# LR1302_LoRaWAN_Gateway_Module_V1_0_868SP.net
KiCad netlist of a schematic drawn in EAGLE
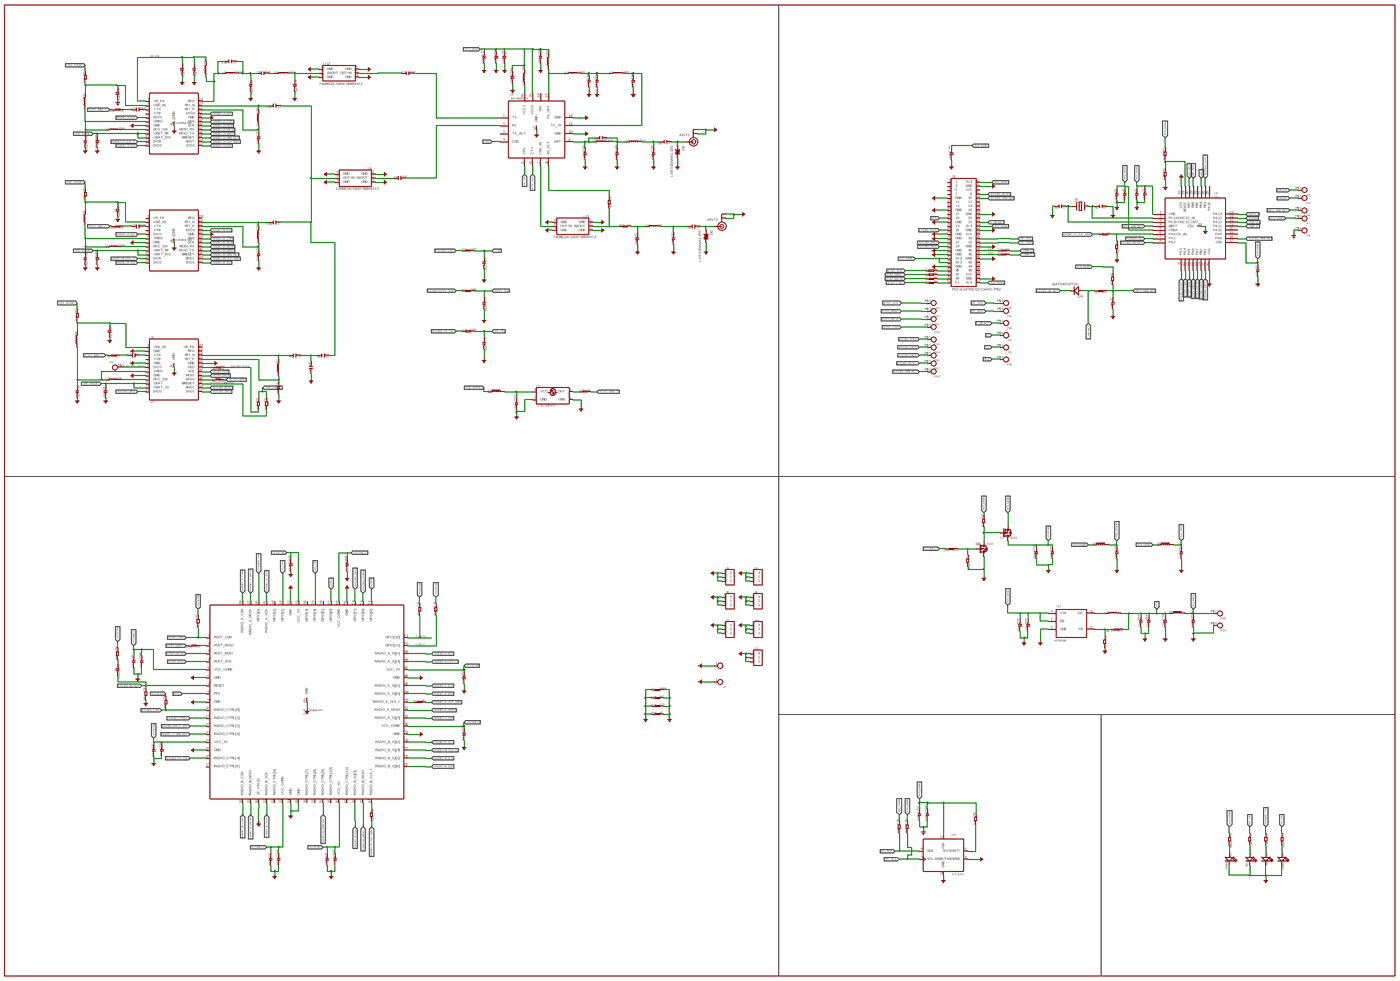
[diagram p0: schematic, sheet 1, overview]
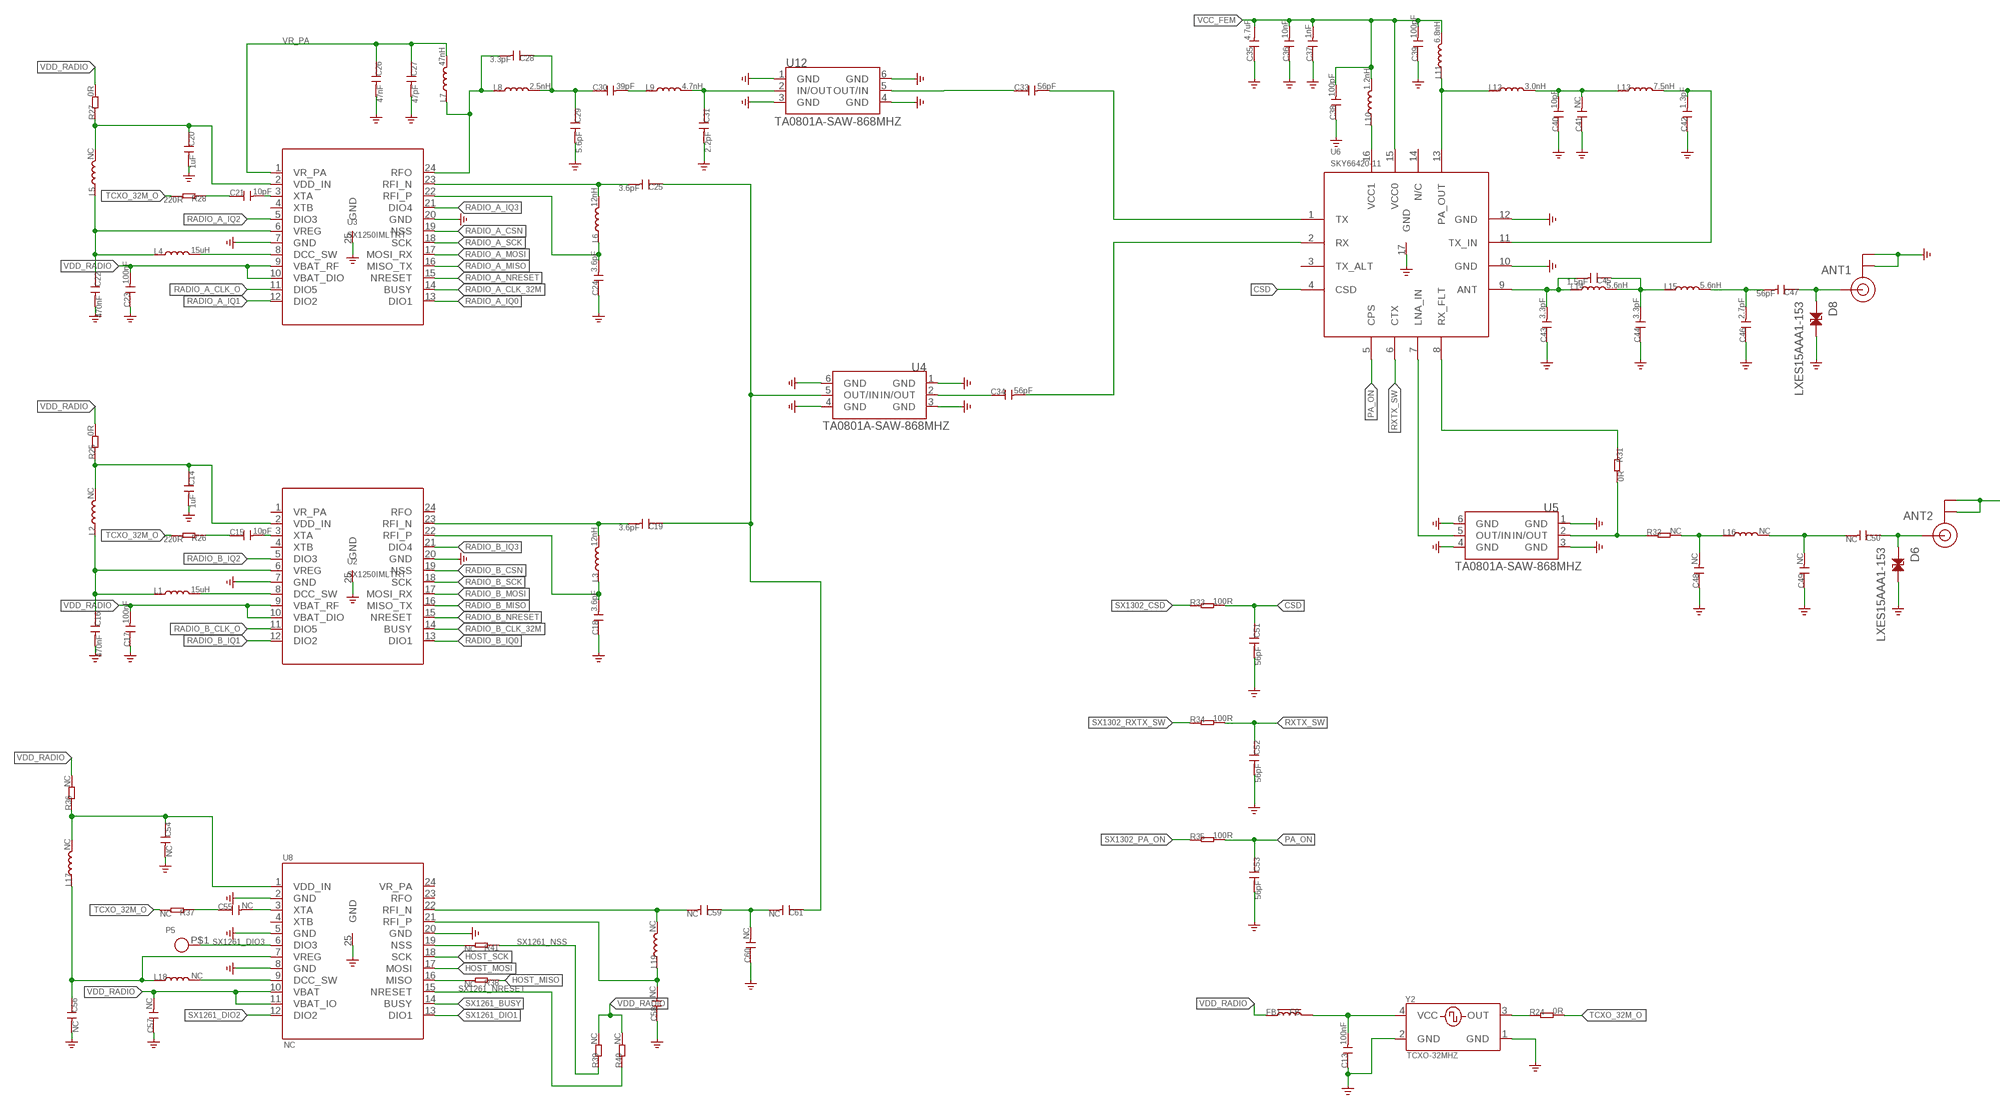
[diagram p1: schematic, sheet 1, part 1 of 4]
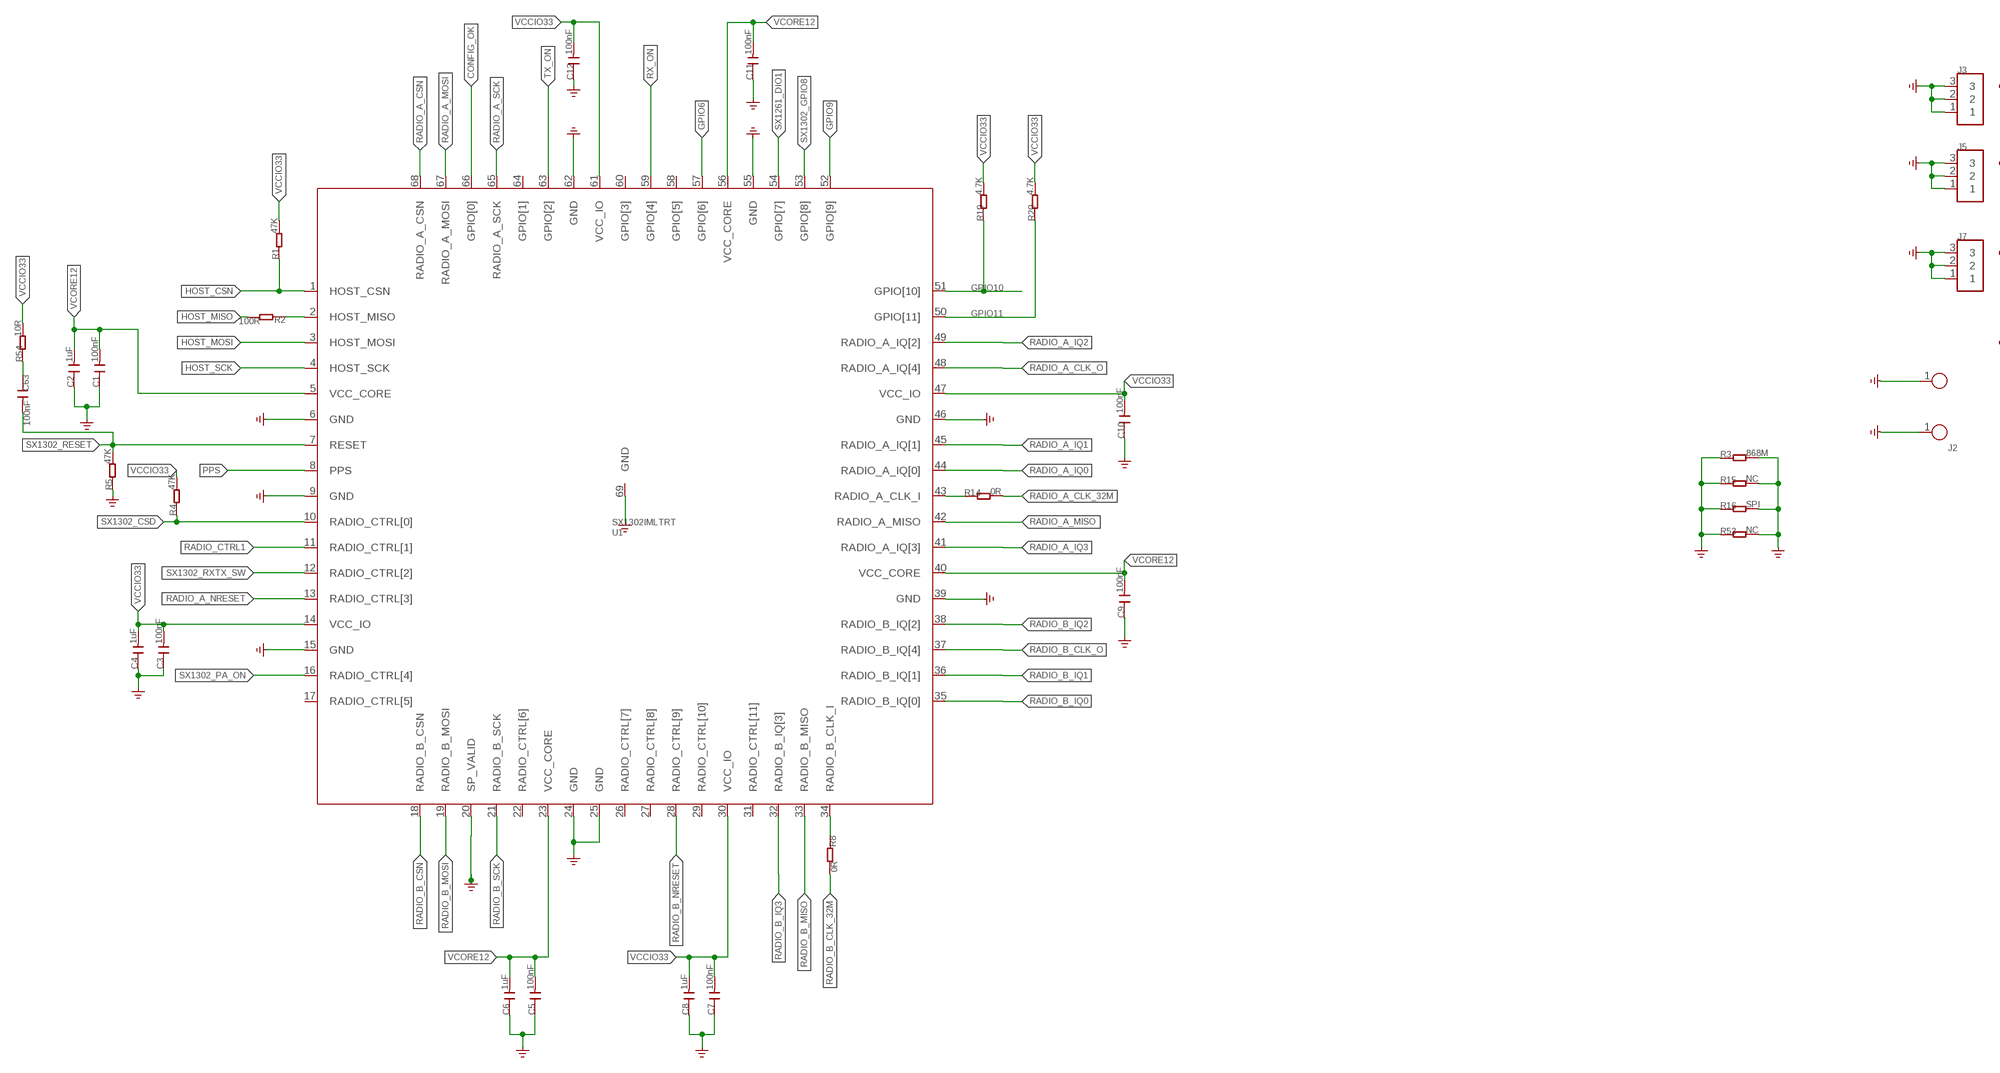
[diagram p2: schematic, sheet 1, part 2 of 4]
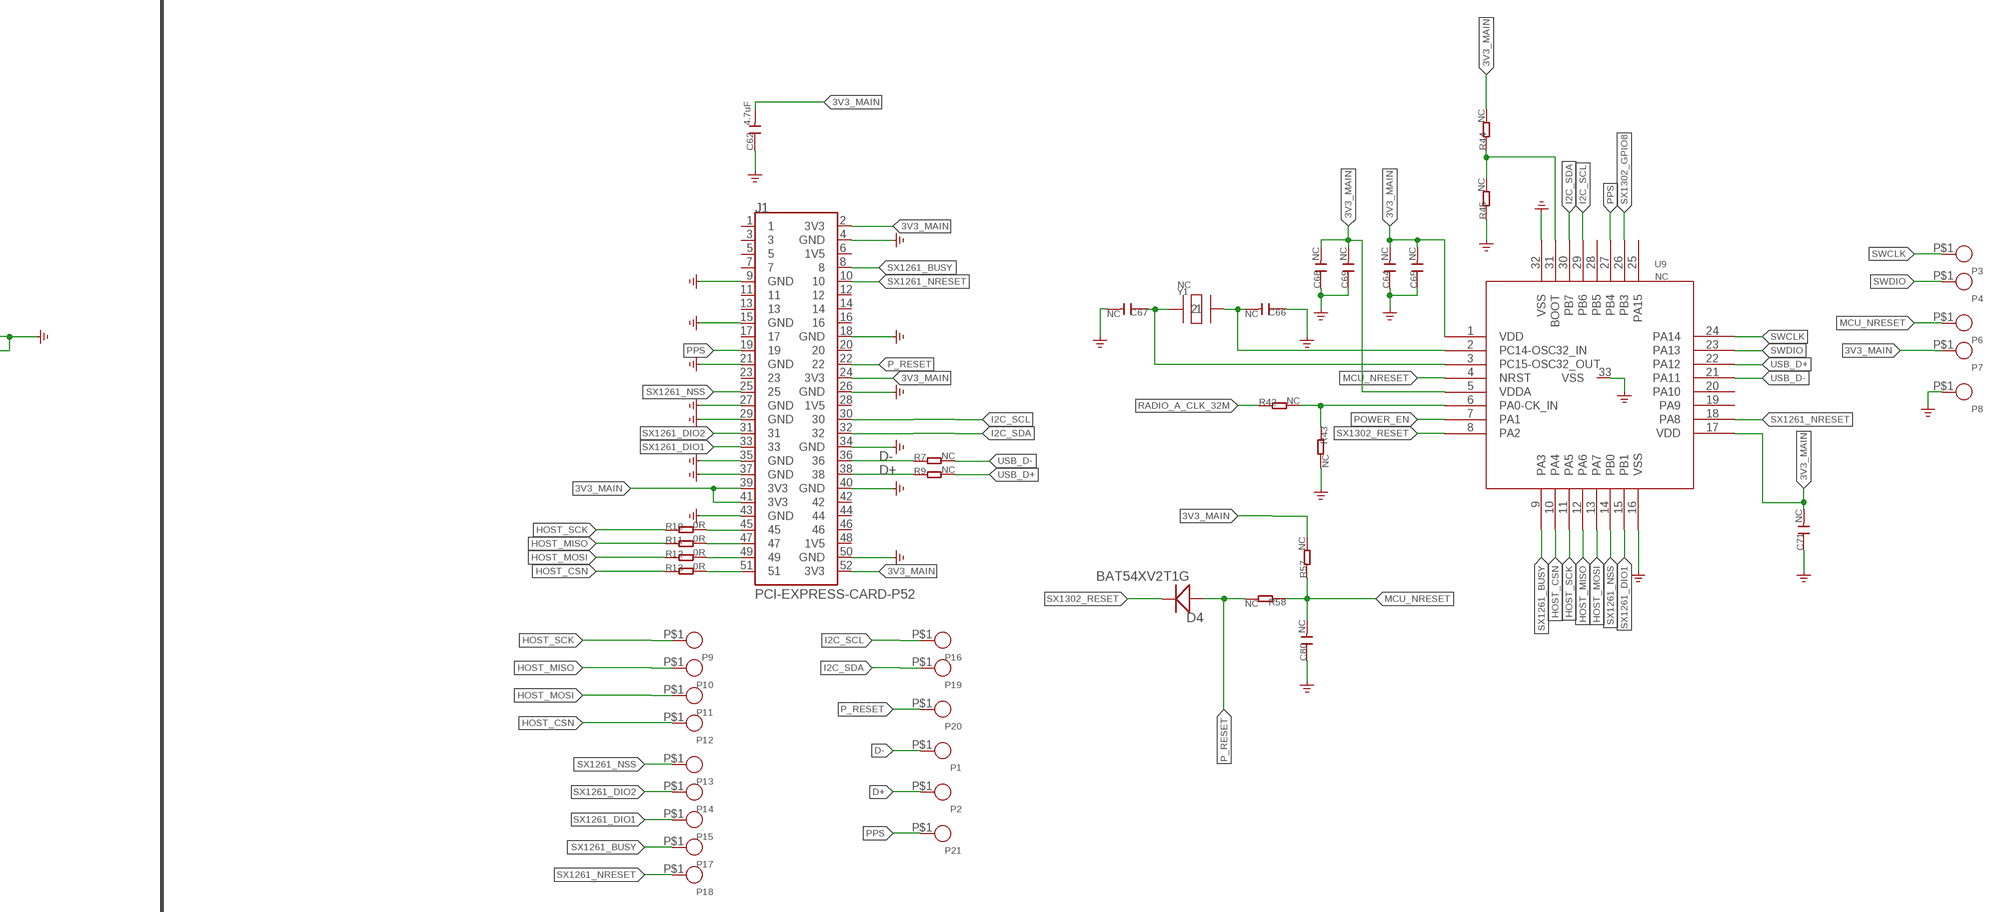
[diagram p3: schematic, sheet 1, part 3 of 4]
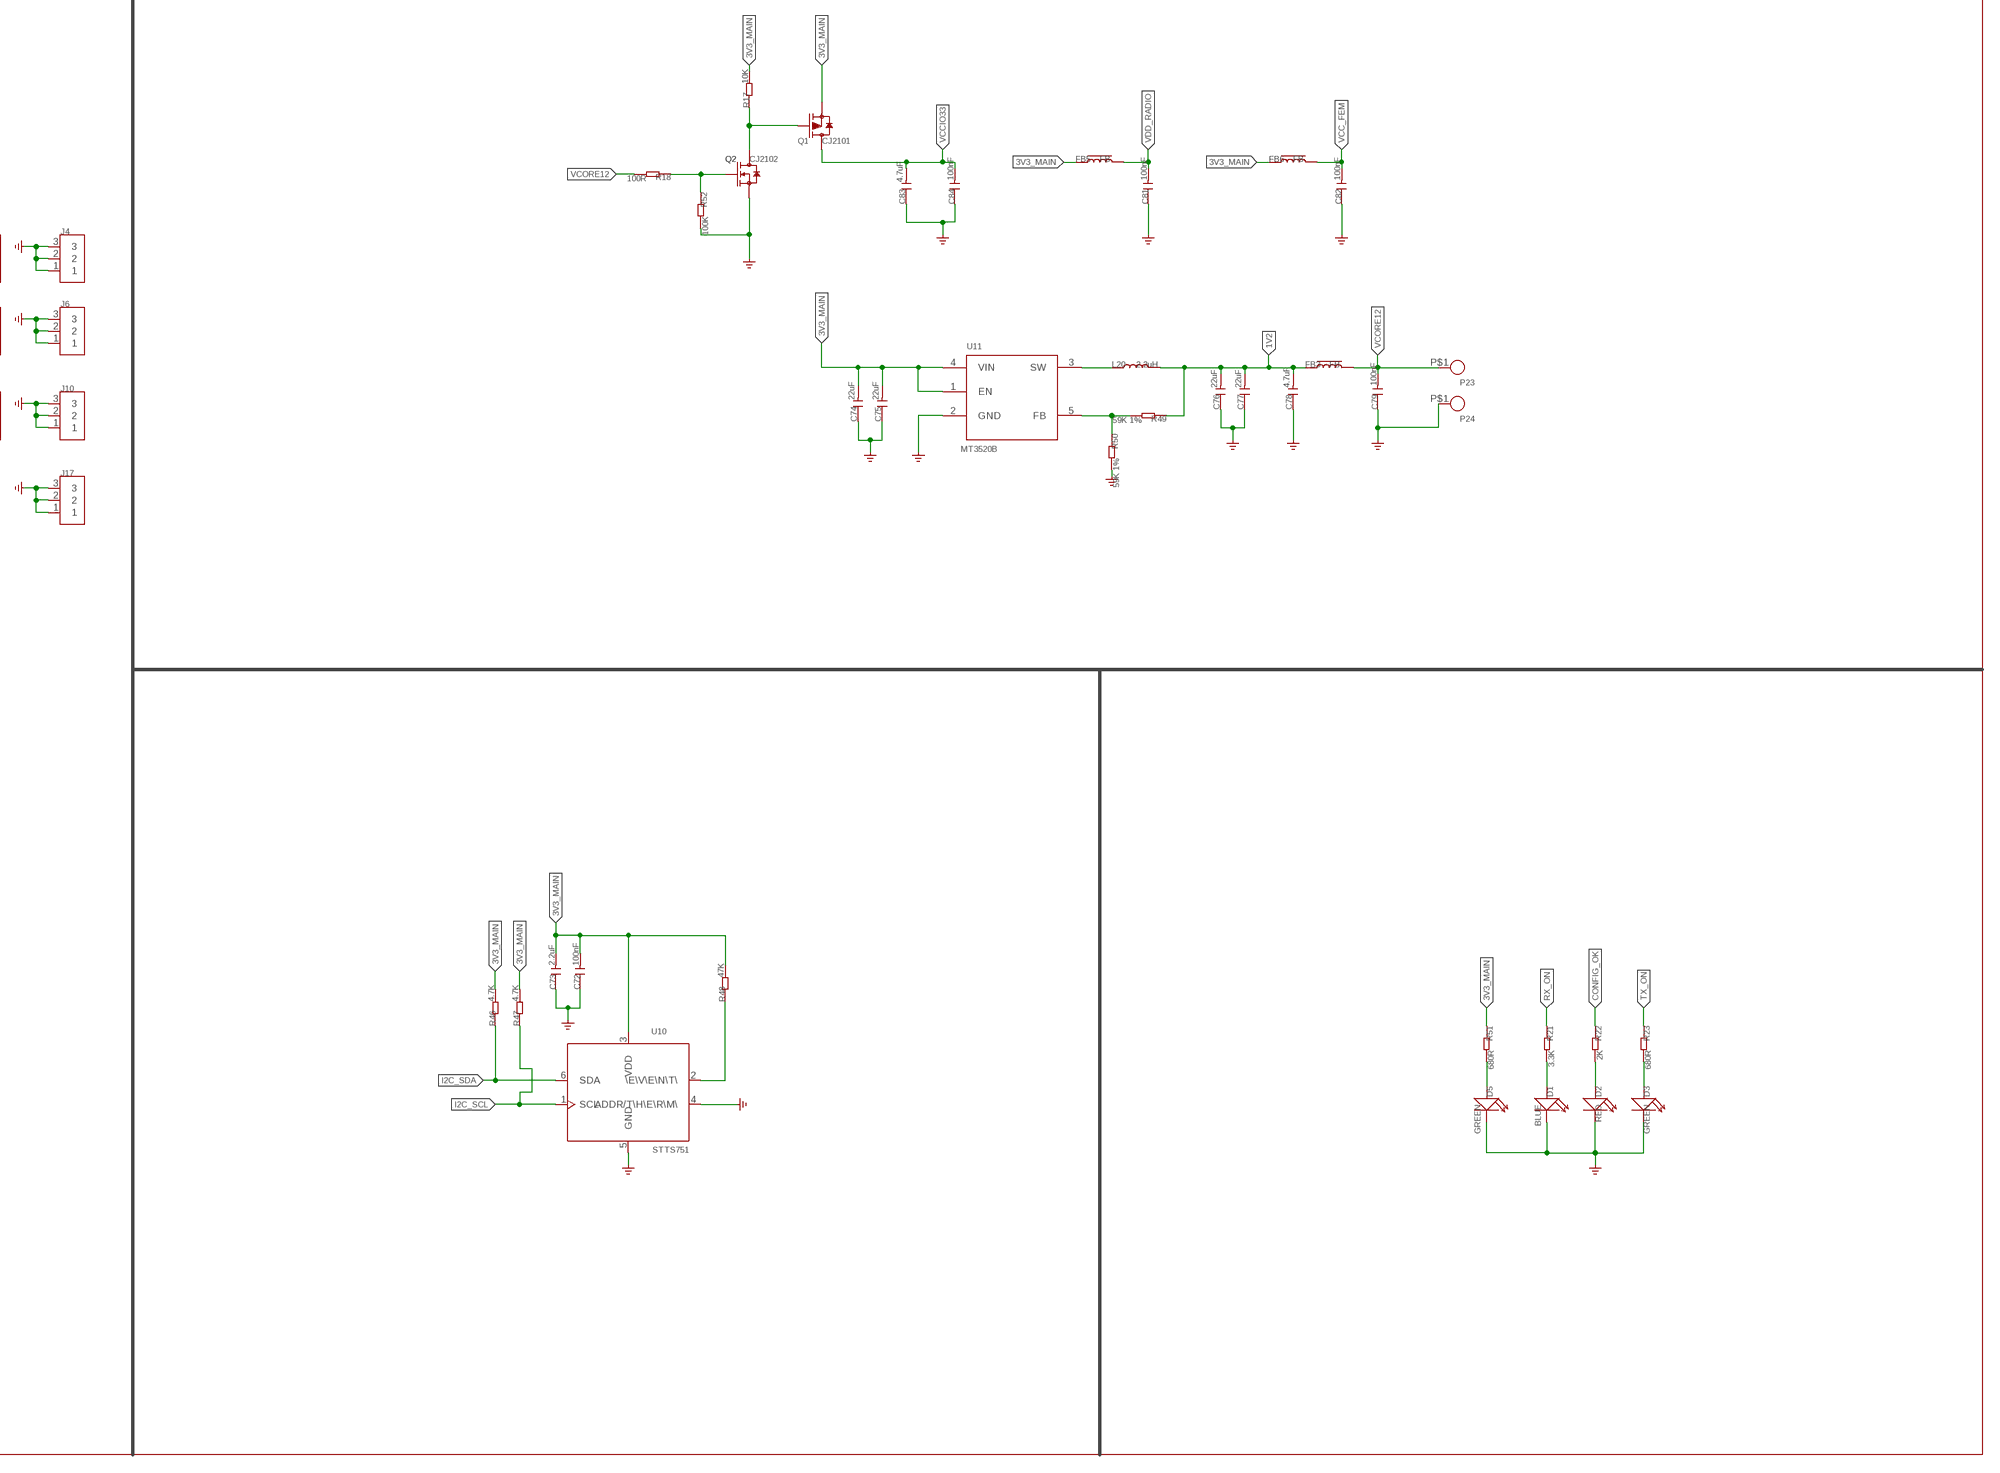
[diagram p4: schematic, sheet 1, part 4 of 4]

(export (version "E")
  (design (tool "Eeschema 10.0.6"))
  (components
    (comp (ref "ANT1")
      (value "U.FL_SMTU.FL-R-SMD")
      (footprint "eagle-import:U.FL-R-SMD")
      (libsource (lib "eagle-import") (part "U.FL_SMTU.FL-R-SMD"))
    )
    (comp (ref "ANT2")
      (value "NC")
      (footprint "eagle-import:U.FL-R-SMD")
      (libsource (lib "eagle-import") (part "U.FL_SMTU.FL-R-SMD"))
    )
    (comp (ref "C1")
      (value "100nF")
      (footprint "eagle-import:C0402")
      (libsource (lib "eagle-import") (part "CAPC0402-1"))
    )
    (comp (ref "C2")
      (value "1uF")
      (footprint "eagle-import:C0402")
      (libsource (lib "eagle-import") (part "CAPC0402-1"))
    )
    (comp (ref "C3")
      (value "100nF")
      (footprint "eagle-import:C0402")
      (libsource (lib "eagle-import") (part "CAPC0402-1"))
    )
    (comp (ref "C4")
      (value "1uF")
      (footprint "eagle-import:C0402")
      (libsource (lib "eagle-import") (part "CAPC0402-1"))
    )
    (comp (ref "C5")
      (value "100nF")
      (footprint "eagle-import:C0402")
      (libsource (lib "eagle-import") (part "CAPC0402-1"))
    )
    (comp (ref "C6")
      (value "1uF")
      (footprint "eagle-import:C0402")
      (libsource (lib "eagle-import") (part "CAPC0402-1"))
    )
    (comp (ref "C7")
      (value "100nF")
      (footprint "eagle-import:C0402")
      (libsource (lib "eagle-import") (part "CAPC0402-1"))
    )
    (comp (ref "C8")
      (value "1uF")
      (footprint "eagle-import:C0402")
      (libsource (lib "eagle-import") (part "CAPC0402-1"))
    )
    (comp (ref "C9")
      (value "100nF")
      (footprint "eagle-import:C0402")
      (libsource (lib "eagle-import") (part "CAPC0402-1"))
    )
    (comp (ref "C10")
      (value "100nF")
      (footprint "eagle-import:C0402")
      (libsource (lib "eagle-import") (part "CAPC0402-1"))
    )
    (comp (ref "C11")
      (value "100nF")
      (footprint "eagle-import:C0402")
      (libsource (lib "eagle-import") (part "CAPC0402-1"))
    )
    (comp (ref "C12")
      (value "100nF")
      (footprint "eagle-import:C0402")
      (libsource (lib "eagle-import") (part "CAPC0402-1"))
    )
    (comp (ref "C13")
      (value "100nF")
      (footprint "eagle-import:C0402")
      (libsource (lib "eagle-import") (part "CAPC0402-1"))
    )
    (comp (ref "C14")
      (value "1uF")
      (footprint "eagle-import:C0402")
      (libsource (lib "eagle-import") (part "CAPC0402-1"))
    )
    (comp (ref "C15")
      (value "10pF")
      (footprint "eagle-import:C0402")
      (libsource (lib "eagle-import") (part "CAPC0402-1"))
    )
    (comp (ref "C16")
      (value "470nF")
      (footprint "eagle-import:C0402")
      (libsource (lib "eagle-import") (part "CAPC0402-1"))
    )
    (comp (ref "C17")
      (value "100nF")
      (footprint "eagle-import:C0402")
      (libsource (lib "eagle-import") (part "CAPC0402-1"))
    )
    (comp (ref "C18")
      (value "3.6pF")
      (footprint "eagle-import:C0402")
      (libsource (lib "eagle-import") (part "CAPC0402-1"))
    )
    (comp (ref "C19")
      (value "3.6pF")
      (footprint "eagle-import:C0402")
      (libsource (lib "eagle-import") (part "CAPC0402-1"))
    )
    (comp (ref "C20")
      (value "1uF")
      (footprint "eagle-import:C0402")
      (libsource (lib "eagle-import") (part "CAPC0402-1"))
    )
    (comp (ref "C21")
      (value "10pF")
      (footprint "eagle-import:C0402")
      (libsource (lib "eagle-import") (part "CAPC0402-1"))
    )
    (comp (ref "C22")
      (value "470nF")
      (footprint "eagle-import:C0402")
      (libsource (lib "eagle-import") (part "CAPC0402-1"))
    )
    (comp (ref "C23")
      (value "100nF")
      (footprint "eagle-import:C0402")
      (libsource (lib "eagle-import") (part "CAPC0402-1"))
    )
    (comp (ref "C24")
      (value "3.6pF")
      (footprint "eagle-import:C0402")
      (libsource (lib "eagle-import") (part "CAPC0402-1"))
    )
    (comp (ref "C25")
      (value "3.6pF")
      (footprint "eagle-import:C0402")
      (libsource (lib "eagle-import") (part "CAPC0402-1"))
    )
    (comp (ref "C26")
      (value "47nF")
      (footprint "eagle-import:C0402")
      (libsource (lib "eagle-import") (part "CAPC0402-1"))
    )
    (comp (ref "C27")
      (value "47pF")
      (footprint "eagle-import:C0402")
      (libsource (lib "eagle-import") (part "CAPC0402-1"))
    )
    (comp (ref "C28")
      (value "3.3pF")
      (footprint "eagle-import:C0402")
      (libsource (lib "eagle-import") (part "CAPC0402-1"))
    )
    (comp (ref "C29")
      (value "5.6pF")
      (footprint "eagle-import:C0402")
      (libsource (lib "eagle-import") (part "CAPC0402-1"))
    )
    (comp (ref "C30")
      (value "39pF")
      (footprint "eagle-import:C0402")
      (libsource (lib "eagle-import") (part "CAPC0402-1"))
    )
    (comp (ref "C31")
      (value "2.2pF")
      (footprint "eagle-import:C0402")
      (libsource (lib "eagle-import") (part "CAPC0402-1"))
    )
    (comp (ref "C33")
      (value "56pF")
      (footprint "eagle-import:C0402")
      (libsource (lib "eagle-import") (part "CAPC0402-1"))
    )
    (comp (ref "C34")
      (value "56pF")
      (footprint "eagle-import:C0402")
      (libsource (lib "eagle-import") (part "CAPC0402-1"))
    )
    (comp (ref "C35")
      (value "4.7uF")
      (footprint "eagle-import:C0603")
      (libsource (lib "eagle-import") (part "CAP"))
    )
    (comp (ref "C36")
      (value "10nF")
      (footprint "eagle-import:C0402")
      (libsource (lib "eagle-import") (part "CAPC0402-1"))
    )
    (comp (ref "C37")
      (value "1nF")
      (footprint "eagle-import:C0402")
      (libsource (lib "eagle-import") (part "CAPC0402-1"))
    )
    (comp (ref "C38")
      (value "100pF")
      (footprint "eagle-import:C0402")
      (libsource (lib "eagle-import") (part "CAPC0402-1"))
    )
    (comp (ref "C39")
      (value "100pF")
      (footprint "eagle-import:C0402")
      (libsource (lib "eagle-import") (part "CAPC0402-1"))
    )
    (comp (ref "C40")
      (value "10pF")
      (footprint "eagle-import:C0402")
      (libsource (lib "eagle-import") (part "CAPC0402-1"))
    )
    (comp (ref "C41")
      (value "NC")
      (footprint "eagle-import:C0402")
      (libsource (lib "eagle-import") (part "CAPC0402-1"))
    )
    (comp (ref "C42")
      (value "1.3pF")
      (footprint "eagle-import:C0402")
      (libsource (lib "eagle-import") (part "CAPC0402-1"))
    )
    (comp (ref "C43")
      (value "3.3pF")
      (footprint "eagle-import:C0402")
      (libsource (lib "eagle-import") (part "CAPC0402-1"))
    )
    (comp (ref "C44")
      (value "3.3pF")
      (footprint "eagle-import:C0402")
      (libsource (lib "eagle-import") (part "CAPC0402-1"))
    )
    (comp (ref "C45")
      (value "1.5pF")
      (footprint "eagle-import:C0402")
      (libsource (lib "eagle-import") (part "CAPC0402-1"))
    )
    (comp (ref "C46")
      (value "2.7pF")
      (footprint "eagle-import:C0402")
      (libsource (lib "eagle-import") (part "CAPC0402-1"))
    )
    (comp (ref "C47")
      (value "56pF")
      (footprint "eagle-import:C0402")
      (libsource (lib "eagle-import") (part "CAPC0402-1"))
    )
    (comp (ref "C48")
      (value "NC")
      (footprint "eagle-import:C0402")
      (libsource (lib "eagle-import") (part "CAPC0402-1"))
    )
    (comp (ref "C49")
      (value "NC")
      (footprint "eagle-import:C0402")
      (libsource (lib "eagle-import") (part "CAPC0402-1"))
    )
    (comp (ref "C50")
      (value "NC")
      (footprint "eagle-import:C0402")
      (libsource (lib "eagle-import") (part "CAPC0402-1"))
    )
    (comp (ref "C51")
      (value "56pF")
      (footprint "eagle-import:C0402")
      (libsource (lib "eagle-import") (part "CAPC0402-1"))
    )
    (comp (ref "C52")
      (value "56pF")
      (footprint "eagle-import:C0402")
      (libsource (lib "eagle-import") (part "CAPC0402-1"))
    )
    (comp (ref "C53")
      (value "56pF")
      (footprint "eagle-import:C0402")
      (libsource (lib "eagle-import") (part "CAPC0402-1"))
    )
    (comp (ref "C54")
      (value "NC")
      (footprint "eagle-import:C0402")
      (libsource (lib "eagle-import") (part "CAPC0402-1"))
    )
    (comp (ref "C55")
      (value "NC")
      (footprint "eagle-import:C0402")
      (libsource (lib "eagle-import") (part "CAPC0402-1"))
    )
    (comp (ref "C56")
      (value "NC")
      (footprint "eagle-import:C0402")
      (libsource (lib "eagle-import") (part "CAPC0402-1"))
    )
    (comp (ref "C57")
      (value "NC")
      (footprint "eagle-import:C0402")
      (libsource (lib "eagle-import") (part "CAPC0402-1"))
    )
    (comp (ref "C58")
      (value "NC")
      (footprint "eagle-import:C0402")
      (libsource (lib "eagle-import") (part "CAPC0402-1"))
    )
    (comp (ref "C59")
      (value "NC")
      (footprint "eagle-import:C0402")
      (libsource (lib "eagle-import") (part "CAPC0402-1"))
    )
    (comp (ref "C60")
      (value "NC")
      (footprint "eagle-import:C0402")
      (libsource (lib "eagle-import") (part "CAPC0402-1"))
    )
    (comp (ref "C61")
      (value "NC")
      (footprint "eagle-import:C0402")
      (libsource (lib "eagle-import") (part "CAPC0402-1"))
    )
    (comp (ref "C62")
      (value "4.7uF")
      (footprint "eagle-import:C0603")
      (libsource (lib "eagle-import") (part "CAP"))
    )
    (comp (ref "C63")
      (value "100nF")
      (footprint "eagle-import:C0402")
      (libsource (lib "eagle-import") (part "CAPC0402-1"))
    )
    (comp (ref "C64")
      (value "NC")
      (footprint "eagle-import:C0402")
      (libsource (lib "eagle-import") (part "CAPC0402-1"))
    )
    (comp (ref "C65")
      (value "NC")
      (footprint "eagle-import:C0402")
      (libsource (lib "eagle-import") (part "CAPC0402-1"))
    )
    (comp (ref "C66")
      (value "NC")
      (footprint "eagle-import:C0402")
      (libsource (lib "eagle-import") (part "CAPC0402-1"))
    )
    (comp (ref "C67")
      (value "NC")
      (footprint "eagle-import:C0402")
      (libsource (lib "eagle-import") (part "CAPC0402-1"))
    )
    (comp (ref "C68")
      (value "NC")
      (footprint "eagle-import:C0402")
      (libsource (lib "eagle-import") (part "CAPC0402-1"))
    )
    (comp (ref "C69")
      (value "NC")
      (footprint "eagle-import:C0402")
      (libsource (lib "eagle-import") (part "CAPC0402-1"))
    )
    (comp (ref "C71")
      (value "NC")
      (footprint "eagle-import:C0402")
      (libsource (lib "eagle-import") (part "CAPC0402-1"))
    )
    (comp (ref "C72")
      (value "100nF")
      (footprint "eagle-import:C0402")
      (libsource (lib "eagle-import") (part "CAPC0402-1"))
    )
    (comp (ref "C73")
      (value "2.2uF")
      (footprint "eagle-import:C0402")
      (libsource (lib "eagle-import") (part "CAPC0402-1"))
    )
    (comp (ref "C74")
      (value "22uF")
      (footprint "eagle-import:C0603")
      (libsource (lib "eagle-import") (part "CAP"))
    )
    (comp (ref "C75")
      (value "22uF")
      (footprint "eagle-import:C0603")
      (libsource (lib "eagle-import") (part "CAP"))
    )
    (comp (ref "C76")
      (value "22uF")
      (footprint "eagle-import:C0603")
      (libsource (lib "eagle-import") (part "CAP"))
    )
    (comp (ref "C77")
      (value "22uF")
      (footprint "eagle-import:C0603")
      (libsource (lib "eagle-import") (part "CAP"))
    )
    (comp (ref "C78")
      (value "4.7uF")
      (footprint "eagle-import:C0603")
      (libsource (lib "eagle-import") (part "CAP"))
    )
    (comp (ref "C79")
      (value "100nF")
      (footprint "eagle-import:C0402")
      (libsource (lib "eagle-import") (part "CAPC0402-1"))
    )
    (comp (ref "C80")
      (value "NC")
      (footprint "eagle-import:C0402")
      (libsource (lib "eagle-import") (part "CAPC0402-1"))
    )
    (comp (ref "C81")
      (value "100nF")
      (footprint "eagle-import:C0402")
      (libsource (lib "eagle-import") (part "CAPC0402-1"))
    )
    (comp (ref "C82")
      (value "100nF")
      (footprint "eagle-import:C0402")
      (libsource (lib "eagle-import") (part "CAPC0402-1"))
    )
    (comp (ref "C83")
      (value "4.7uF")
      (footprint "eagle-import:C0603")
      (libsource (lib "eagle-import") (part "CAP"))
    )
    (comp (ref "C84")
      (value "100nF")
      (footprint "eagle-import:C0402")
      (libsource (lib "eagle-import") (part "CAPC0402-1"))
    )
    (comp (ref "D1")
      (value "BLUE")
      (footprint "eagle-import:LED-0402")
      (libsource (lib "eagle-import") (part "LED-SMT"))
    )
    (comp (ref "D2")
      (value "RED")
      (footprint "eagle-import:LED-0402")
      (libsource (lib "eagle-import") (part "LED-SMT"))
    )
    (comp (ref "D3")
      (value "GREEN")
      (footprint "eagle-import:LED-0402")
      (libsource (lib "eagle-import") (part "LED-SMT"))
    )
    (comp (ref "D4")
      (value "BAT54XV2T1G")
      (footprint "eagle-import:D_SOD523")
      (libsource (lib "eagle-import") (part "DIODE0603"))
    )
    (comp (ref "D5")
      (value "GREEN")
      (footprint "eagle-import:LED-0402")
      (libsource (lib "eagle-import") (part "LED-SMT"))
    )
    (comp (ref "D6")
      (value "LXES15AAA1-153")
      (footprint "eagle-import:D0402")
      (libsource (lib "eagle-import") (part "PESD0402"))
    )
    (comp (ref "D8")
      (value "LXES15AAA1-153")
      (footprint "eagle-import:D0402")
      (libsource (lib "eagle-import") (part "PESD0402"))
    )
    (comp (ref "FB1")
      (value "FB")
      (footprint "eagle-import:L0402")
      (libsource (lib "eagle-import") (part "FB"))
    )
    (comp (ref "FB3")
      (value "FB")
      (footprint "eagle-import:L0402")
      (libsource (lib "eagle-import") (part "FB"))
    )
    (comp (ref "FB5")
      (value "FB")
      (footprint "eagle-import:L0402")
      (libsource (lib "eagle-import") (part "FB"))
    )
    (comp (ref "FB6")
      (value "FB")
      (footprint "eagle-import:L0402")
      (libsource (lib "eagle-import") (part "FB"))
    )
    (comp (ref "J1")
      (value "PCI-EXPRESS-CARD-P52")
      (footprint "eagle-import:PCIE-MINI-S52")
      (libsource (lib "eagle-import") (part "PCI-EXPRESS-CARD-P52"))
    )
    (comp (ref "J2")
      (value "PAD-THO-2.65MM")
      (footprint "eagle-import:PAD-THO-2.6_5MM")
      (libsource (lib "eagle-import") (part "PAD-THO-2.65MM"))
    )
    (comp (ref "J3")
      (value "PBJ-ICSRC6508-SMD")
      (footprint "eagle-import:PBJ-ICSRC6508-SMD")
      (libsource (lib "eagle-import") (part "PBJ-ICSRC6508-SMD"))
    )
    (comp (ref "J4")
      (value "PBJ-ICSRC6508-SMD")
      (footprint "eagle-import:PBJ-ICSRC6508-SMD")
      (libsource (lib "eagle-import") (part "PBJ-ICSRC6508-SMD"))
    )
    (comp (ref "J5")
      (value "PBJ-ICSRC6508-SMD")
      (footprint "eagle-import:PBJ-ICSRC6508-SMD")
      (libsource (lib "eagle-import") (part "PBJ-ICSRC6508-SMD"))
    )
    (comp (ref "J6")
      (value "PBJ-ICSRC6508-SMD")
      (footprint "eagle-import:PBJ-ICSRC6508-SMD")
      (libsource (lib "eagle-import") (part "PBJ-ICSRC6508-SMD"))
    )
    (comp (ref "J7")
      (value "PBJ-ICSRC6508-SMD")
      (footprint "eagle-import:PBJ-ICSRC6508-SMD")
      (libsource (lib "eagle-import") (part "PBJ-ICSRC6508-SMD"))
    )
    (comp (ref "J10")
      (value "PBJ-ICSRC6508-SMD")
      (footprint "eagle-import:PBJ-ICSRC6508-SMD")
      (libsource (lib "eagle-import") (part "PBJ-ICSRC6508-SMD"))
    )
    (comp (ref "J11")
      (value "PAD-THO-2.65MM")
      (footprint "eagle-import:PAD-THO-2.6_5MM")
      (libsource (lib "eagle-import") (part "PAD-THO-2.65MM"))
    )
    (comp (ref "J17")
      (value "PBJ-ICSRC6508-SMD")
      (footprint "eagle-import:PBJ-ICSRC6508-SMD")
      (libsource (lib "eagle-import") (part "PBJ-ICSRC6508-SMD"))
    )
    (comp (ref "L1")
      (value "15uH")
      (footprint "eagle-import:L0805")
      (libsource (lib "eagle-import") (part "L0805"))
    )
    (comp (ref "L2")
      (value "NC")
      (footprint "eagle-import:L0402")
      (libsource (lib "eagle-import") (part "L0402"))
    )
    (comp (ref "L3")
      (value "12nH")
      (footprint "eagle-import:L0402")
      (libsource (lib "eagle-import") (part "L0402"))
    )
    (comp (ref "L4")
      (value "15uH")
      (footprint "eagle-import:L0805")
      (libsource (lib "eagle-import") (part "L0805"))
    )
    (comp (ref "L5")
      (value "NC")
      (footprint "eagle-import:L0402")
      (libsource (lib "eagle-import") (part "L0402"))
    )
    (comp (ref "L6")
      (value "12nH")
      (footprint "eagle-import:L0402")
      (libsource (lib "eagle-import") (part "L0402"))
    )
    (comp (ref "L7")
      (value "47nH")
      (footprint "eagle-import:L0402")
      (libsource (lib "eagle-import") (part "L0402"))
    )
    (comp (ref "L8")
      (value "2.5nH")
      (footprint "eagle-import:L0402")
      (libsource (lib "eagle-import") (part "L0402"))
    )
    (comp (ref "L9")
      (value "4.7nH")
      (footprint "eagle-import:L0402")
      (libsource (lib "eagle-import") (part "L0402"))
    )
    (comp (ref "L10")
      (value "1.2nH")
      (footprint "eagle-import:L0402")
      (libsource (lib "eagle-import") (part "L0402"))
    )
    (comp (ref "L11")
      (value "6.8nH")
      (footprint "eagle-import:L0402")
      (libsource (lib "eagle-import") (part "L0402"))
    )
    (comp (ref "L12")
      (value "3.0nH")
      (footprint "eagle-import:L0402")
      (libsource (lib "eagle-import") (part "L0402"))
    )
    (comp (ref "L13")
      (value "7.5nH")
      (footprint "eagle-import:L0402")
      (libsource (lib "eagle-import") (part "L0402"))
    )
    (comp (ref "L14")
      (value "5.6nH")
      (footprint "eagle-import:L0402")
      (libsource (lib "eagle-import") (part "L0402"))
    )
    (comp (ref "L15")
      (value "5.6nH")
      (footprint "eagle-import:L0402")
      (libsource (lib "eagle-import") (part "L0402"))
    )
    (comp (ref "L16")
      (value "NC")
      (footprint "eagle-import:L0402")
      (libsource (lib "eagle-import") (part "L0402"))
    )
    (comp (ref "L17")
      (value "NC")
      (footprint "eagle-import:L0402")
      (libsource (lib "eagle-import") (part "L0402"))
    )
    (comp (ref "L18")
      (value "NC")
      (footprint "eagle-import:L0805")
      (libsource (lib "eagle-import") (part "L0805"))
    )
    (comp (ref "L19")
      (value "NC")
      (footprint "eagle-import:L0402")
      (libsource (lib "eagle-import") (part "L0402"))
    )
    (comp (ref "L20")
      (value "2.2uH")
      (footprint "eagle-import:L3015_SMD")
      (libsource (lib "eagle-import") (part "L"))
    )
    (comp (ref "P1")
      (value "TEST_PADPAD-1.0MM")
      (footprint "eagle-import:TEST_PAD-1.0MM")
      (libsource (lib "eagle-import") (part "TEST_PADPAD-1.0MM"))
    )
    (comp (ref "P2")
      (value "TEST_PADPAD-1.0MM")
      (footprint "eagle-import:TEST_PAD-1.0MM")
      (libsource (lib "eagle-import") (part "TEST_PADPAD-1.0MM"))
    )
    (comp (ref "P3")
      (value "TEST_PADPAD-1.0MM")
      (footprint "eagle-import:TEST_PAD-1.0MM")
      (libsource (lib "eagle-import") (part "TEST_PADPAD-1.0MM"))
    )
    (comp (ref "P4")
      (value "TEST_PADPAD-1.0MM")
      (footprint "eagle-import:TEST_PAD-1.0MM")
      (libsource (lib "eagle-import") (part "TEST_PADPAD-1.0MM"))
    )
    (comp (ref "P5")
      (value "TEST_PADPAD-1.0MM")
      (footprint "eagle-import:TEST_PAD-1.0MM")
      (libsource (lib "eagle-import") (part "TEST_PADPAD-1.0MM"))
    )
    (comp (ref "P6")
      (value "TEST_PADPAD-1.0MM")
      (footprint "eagle-import:TEST_PAD-1.0MM")
      (libsource (lib "eagle-import") (part "TEST_PADPAD-1.0MM"))
    )
    (comp (ref "P7")
      (value "TEST_PADPAD-1.0MM")
      (footprint "eagle-import:TEST_PAD-1.0MM")
      (libsource (lib "eagle-import") (part "TEST_PADPAD-1.0MM"))
    )
    (comp (ref "P8")
      (value "TEST_PADPAD-1.0MM")
      (footprint "eagle-import:TEST_PAD-1.0MM")
      (libsource (lib "eagle-import") (part "TEST_PADPAD-1.0MM"))
    )
    (comp (ref "P9")
      (value "TEST_PADPAD-1.0MM")
      (footprint "eagle-import:TEST_PAD-1.0MM")
      (libsource (lib "eagle-import") (part "TEST_PADPAD-1.0MM"))
    )
    (comp (ref "P10")
      (value "TEST_PADPAD-1.0MM")
      (footprint "eagle-import:TEST_PAD-1.0MM")
      (libsource (lib "eagle-import") (part "TEST_PADPAD-1.0MM"))
    )
    (comp (ref "P11")
      (value "TEST_PADPAD-1.0MM")
      (footprint "eagle-import:TEST_PAD-1.0MM")
      (libsource (lib "eagle-import") (part "TEST_PADPAD-1.0MM"))
    )
    (comp (ref "P12")
      (value "TEST_PADPAD-1.0MM")
      (footprint "eagle-import:TEST_PAD-1.0MM")
      (libsource (lib "eagle-import") (part "TEST_PADPAD-1.0MM"))
    )
    (comp (ref "P13")
      (value "TEST_PADPAD-1.0MM")
      (footprint "eagle-import:TEST_PAD-1.0MM")
      (libsource (lib "eagle-import") (part "TEST_PADPAD-1.0MM"))
    )
    (comp (ref "P14")
      (value "TEST_PADPAD-1.0MM")
      (footprint "eagle-import:TEST_PAD-1.0MM")
      (libsource (lib "eagle-import") (part "TEST_PADPAD-1.0MM"))
    )
    (comp (ref "P15")
      (value "TEST_PADPAD-1.0MM")
      (footprint "eagle-import:TEST_PAD-1.0MM")
      (libsource (lib "eagle-import") (part "TEST_PADPAD-1.0MM"))
    )
    (comp (ref "P16")
      (value "TEST_PADPAD-1.0MM")
      (footprint "eagle-import:TEST_PAD-1.0MM")
      (libsource (lib "eagle-import") (part "TEST_PADPAD-1.0MM"))
    )
    (comp (ref "P17")
      (value "TEST_PADPAD-1.0MM")
      (footprint "eagle-import:TEST_PAD-1.0MM")
      (libsource (lib "eagle-import") (part "TEST_PADPAD-1.0MM"))
    )
    (comp (ref "P18")
      (value "TEST_PADPAD-1.0MM")
      (footprint "eagle-import:TEST_PAD-1.0MM")
      (libsource (lib "eagle-import") (part "TEST_PADPAD-1.0MM"))
    )
    (comp (ref "P19")
      (value "TEST_PADPAD-1.0MM")
      (footprint "eagle-import:TEST_PAD-1.0MM")
      (libsource (lib "eagle-import") (part "TEST_PADPAD-1.0MM"))
    )
    (comp (ref "P20")
      (value "TEST_PADPAD-1.0MM")
      (footprint "eagle-import:TEST_PAD-1.0MM")
      (libsource (lib "eagle-import") (part "TEST_PADPAD-1.0MM"))
    )
    (comp (ref "P21")
      (value "TEST_PADPAD-1.0MM")
      (footprint "eagle-import:TEST_PAD-1.0MM")
      (libsource (lib "eagle-import") (part "TEST_PADPAD-1.0MM"))
    )
    (comp (ref "P23")
      (value "TEST_PADPAD-1.0MM")
      (footprint "eagle-import:TEST_PAD-1.0MM")
      (libsource (lib "eagle-import") (part "TEST_PADPAD-1.0MM"))
    )
    (comp (ref "P24")
      (value "TEST_PADPAD-1.0MM")
      (footprint "eagle-import:TEST_PAD-1.0MM")
      (libsource (lib "eagle-import") (part "TEST_PADPAD-1.0MM"))
    )
    (comp (ref "Q1")
      (value "CJ2101")
      (footprint "eagle-import:MOS_SOT323")
      (libsource (lib "eagle-import") (part "MOSFET-P"))
    )
    (comp (ref "Q2")
      (value "CJ2102")
      (footprint "eagle-import:MOS_SOT323")
      (libsource (lib "eagle-import") (part "MOSFET-NSI1304BDL"))
    )
    (comp (ref "R1")
      (value "47K")
      (footprint "eagle-import:R0402")
      (libsource (lib "eagle-import") (part "RES-0402"))
    )
    (comp (ref "R2")
      (value "100R")
      (footprint "eagle-import:R0402")
      (libsource (lib "eagle-import") (part "RES-0402"))
    )
    (comp (ref "R3")
      (value "868M")
      (footprint "eagle-import:R0402")
      (libsource (lib "eagle-import") (part "RES-0402"))
    )
    (comp (ref "R4")
      (value "47K")
      (footprint "eagle-import:R0402")
      (libsource (lib "eagle-import") (part "RES-0402"))
    )
    (comp (ref "R5")
      (value "47K")
      (footprint "eagle-import:R0402")
      (libsource (lib "eagle-import") (part "RES-0402"))
    )
    (comp (ref "R7")
      (value "NC")
      (footprint "eagle-import:R0402")
      (libsource (lib "eagle-import") (part "RES-0402"))
    )
    (comp (ref "R8")
      (value "0R")
      (footprint "eagle-import:R0402")
      (libsource (lib "eagle-import") (part "RES-0402"))
    )
    (comp (ref "R9")
      (value "NC")
      (footprint "eagle-import:R0402")
      (libsource (lib "eagle-import") (part "RES-0402"))
    )
    (comp (ref "R10")
      (value "0R")
      (footprint "eagle-import:R0402")
      (libsource (lib "eagle-import") (part "RES-0402"))
    )
    (comp (ref "R11")
      (value "0R")
      (footprint "eagle-import:R0402")
      (libsource (lib "eagle-import") (part "RES-0402"))
    )
    (comp (ref "R12")
      (value "0R")
      (footprint "eagle-import:R0402")
      (libsource (lib "eagle-import") (part "RES-0402"))
    )
    (comp (ref "R13")
      (value "0R")
      (footprint "eagle-import:R0402")
      (libsource (lib "eagle-import") (part "RES-0402"))
    )
    (comp (ref "R14")
      (value "0R")
      (footprint "eagle-import:R0402")
      (libsource (lib "eagle-import") (part "RES-0402"))
    )
    (comp (ref "R15")
      (value "NC")
      (footprint "eagle-import:R0402")
      (libsource (lib "eagle-import") (part "RES-0402"))
    )
    (comp (ref "R16")
      (value "SPI")
      (footprint "eagle-import:R0402")
      (libsource (lib "eagle-import") (part "RES-0402"))
    )
    (comp (ref "R17")
      (value "10K")
      (footprint "eagle-import:R0402")
      (libsource (lib "eagle-import") (part "RES-0402"))
    )
    (comp (ref "R18")
      (value "100R")
      (footprint "eagle-import:R0402")
      (libsource (lib "eagle-import") (part "RES-0402"))
    )
    (comp (ref "R19")
      (value "4.7K")
      (footprint "eagle-import:R0402")
      (libsource (lib "eagle-import") (part "RES-0402"))
    )
    (comp (ref "R20")
      (value "4.7K")
      (footprint "eagle-import:R0402")
      (libsource (lib "eagle-import") (part "RES-0402"))
    )
    (comp (ref "R21")
      (value "3.3K")
      (footprint "eagle-import:R0402")
      (libsource (lib "eagle-import") (part "RES-0402"))
    )
    (comp (ref "R22")
      (value "2K")
      (footprint "eagle-import:R0402")
      (libsource (lib "eagle-import") (part "RES-0402"))
    )
    (comp (ref "R23")
      (value "680R")
      (footprint "eagle-import:R0402")
      (libsource (lib "eagle-import") (part "RES-0402"))
    )
    (comp (ref "R24")
      (value "0R")
      (footprint "eagle-import:R0402")
      (libsource (lib "eagle-import") (part "RES-0402"))
    )
    (comp (ref "R25")
      (value "0R")
      (footprint "eagle-import:R0402")
      (libsource (lib "eagle-import") (part "RES-0402"))
    )
    (comp (ref "R26")
      (value "220R")
      (footprint "eagle-import:R0402")
      (libsource (lib "eagle-import") (part "RES-0402"))
    )
    (comp (ref "R27")
      (value "0R")
      (footprint "eagle-import:R0402")
      (libsource (lib "eagle-import") (part "RES-0402"))
    )
    (comp (ref "R28")
      (value "220R")
      (footprint "eagle-import:R0402")
      (libsource (lib "eagle-import") (part "RES-0402"))
    )
    (comp (ref "R31")
      (value "0R")
      (footprint "eagle-import:R0402")
      (libsource (lib "eagle-import") (part "RES-0402"))
    )
    (comp (ref "R32")
      (value "NC")
      (footprint "eagle-import:R0402")
      (libsource (lib "eagle-import") (part "RES-0402"))
    )
    (comp (ref "R33")
      (value "100R")
      (footprint "eagle-import:R0402")
      (libsource (lib "eagle-import") (part "RES-0402"))
    )
    (comp (ref "R34")
      (value "100R")
      (footprint "eagle-import:R0402")
      (libsource (lib "eagle-import") (part "RES-0402"))
    )
    (comp (ref "R35")
      (value "100R")
      (footprint "eagle-import:R0402")
      (libsource (lib "eagle-import") (part "RES-0402"))
    )
    (comp (ref "R36")
      (value "NC")
      (footprint "eagle-import:R0402")
      (libsource (lib "eagle-import") (part "RES-0402"))
    )
    (comp (ref "R37")
      (value "NC")
      (footprint "eagle-import:R0402")
      (libsource (lib "eagle-import") (part "RES-0402"))
    )
    (comp (ref "R38")
      (value "NC")
      (footprint "eagle-import:R0402")
      (libsource (lib "eagle-import") (part "RES-0402"))
    )
    (comp (ref "R39")
      (value "NC")
      (footprint "eagle-import:R0402")
      (libsource (lib "eagle-import") (part "RES-0402"))
    )
    (comp (ref "R40")
      (value "NC")
      (footprint "eagle-import:R0402")
      (libsource (lib "eagle-import") (part "RES-0402"))
    )
    (comp (ref "R41")
      (value "NC")
      (footprint "eagle-import:R0402")
      (libsource (lib "eagle-import") (part "RES-0402"))
    )
    (comp (ref "R42")
      (value "NC")
      (footprint "eagle-import:R0402")
      (libsource (lib "eagle-import") (part "RES-0402"))
    )
    (comp (ref "R43")
      (value "NC")
      (footprint "eagle-import:R0402")
      (libsource (lib "eagle-import") (part "RES-0402"))
    )
    (comp (ref "R44")
      (value "NC")
      (footprint "eagle-import:R0402")
      (libsource (lib "eagle-import") (part "RES-0402"))
    )
    (comp (ref "R45")
      (value "NC")
      (footprint "eagle-import:R0402")
      (libsource (lib "eagle-import") (part "RES-0402"))
    )
    (comp (ref "R46")
      (value "4.7K")
      (footprint "eagle-import:R0402")
      (libsource (lib "eagle-import") (part "RES-0402"))
    )
    (comp (ref "R47")
      (value "4.7K")
      (footprint "eagle-import:R0402")
      (libsource (lib "eagle-import") (part "RES-0402"))
    )
    (comp (ref "R48")
      (value "47K")
      (footprint "eagle-import:R0402")
      (libsource (lib "eagle-import") (part "RES-0402"))
    )
    (comp (ref "R49")
      (value "59K 1%")
      (footprint "eagle-import:R0402")
      (libsource (lib "eagle-import") (part "RES-0402"))
    )
    (comp (ref "R50")
      (value "59K 1%")
      (footprint "eagle-import:R0402")
      (libsource (lib "eagle-import") (part "RES-0402"))
    )
    (comp (ref "R51")
      (value "680R")
      (footprint "eagle-import:R0402")
      (libsource (lib "eagle-import") (part "RES-0402"))
    )
    (comp (ref "R52")
      (value "100K")
      (footprint "eagle-import:R0402")
      (libsource (lib "eagle-import") (part "RES-0402"))
    )
    (comp (ref "R53")
      (value "NC")
      (footprint "eagle-import:R0402")
      (libsource (lib "eagle-import") (part "RES-0402"))
    )
    (comp (ref "R54")
      (value "10R")
      (footprint "eagle-import:R0402")
      (libsource (lib "eagle-import") (part "RES-0402"))
    )
    (comp (ref "R57")
      (value "NC")
      (footprint "eagle-import:R0402")
      (libsource (lib "eagle-import") (part "RES-0402"))
    )
    (comp (ref "R58")
      (value "NC")
      (footprint "eagle-import:R0402")
      (libsource (lib "eagle-import") (part "RES-0402"))
    )
    (comp (ref "U1")
      (value "SX1302IMLTRT")
      (footprint "eagle-import:QFN68-7_7MM")
      (libsource (lib "eagle-import") (part "SX1302IMLTRT"))
    )
    (comp (ref "U2")
      (value "SX1250IMLTRT")
      (footprint "eagle-import:QFN24-4_4MM")
      (libsource (lib "eagle-import") (part "SX1250IMLTRT"))
    )
    (comp (ref "U3")
      (value "SX1250IMLTRT")
      (footprint "eagle-import:QFN24-4_4MM")
      (libsource (lib "eagle-import") (part "SX1250IMLTRT"))
    )
    (comp (ref "U4")
      (value "TA0801A-SAW-868MHZ")
      (footprint "eagle-import:SAW-SMD6-3_3MM")
      (libsource (lib "eagle-import") (part "TA0801A-SAW-868MHZ"))
    )
    (comp (ref "U5")
      (value "TA0801A-SAW-868MHZ")
      (footprint "eagle-import:SAW-SMD6-3_3MM")
      (libsource (lib "eagle-import") (part "TA0801A-SAW-868MHZ"))
    )
    (comp (ref "U6")
      (value "SKY66420-11")
      (footprint "eagle-import:MCM-16-EP(3X3)")
      (libsource (lib "eagle-import") (part "SKY66420-11"))
    )
    (comp (ref "U8")
      (value "NC")
      (footprint "eagle-import:QFN24-4_4MM")
      (libsource (lib "eagle-import") (part "SX1261IMLTRT"))
    )
    (comp (ref "U9")
      (value "NC")
      (footprint "eagle-import:UFQFPN-32-5_5MM")
      (libsource (lib "eagle-import") (part "STM32L412KX"))
    )
    (comp (ref "U10")
      (value "STTS751")
      (footprint "eagle-import:UDFN-6(2X2)")
      (libsource (lib "eagle-import") (part "STTS751"))
    )
    (comp (ref "U11")
      (value "MT3520B")
      (footprint "eagle-import:IC_SOT23-5")
      (libsource (lib "eagle-import") (part "MT3520B"))
    )
    (comp (ref "U12")
      (value "TA0801A-SAW-868MHZ")
      (footprint "eagle-import:SAW-SMD6-3_3MM")
      (libsource (lib "eagle-import") (part "TA0801A-SAW-868MHZ"))
    )
    (comp (ref "Y1")
      (value "NC")
      (footprint "eagle-import:XATL-3215-SMD")
      (libsource (lib "eagle-import") (part "XTAL-32.768KHZ"))
    )
    (comp (ref "Y2")
      (value "TCXO-32MHZ")
      (footprint "eagle-import:TXCO-SMD2.0_1.6")
      (libsource (lib "eagle-import") (part "TCXO-32MHZ"))
    )
  )
  (nets
    (net (code "1") (name "/GPIO10") (class "Default")
      (node (ref "R19") (pin "1") (pinfunction "1_1") (pintype "passive"))
      (node (ref "U1") (pin "51") (pinfunction "GPIO[10]_51") (pintype "passive"))
    )
    (net (code "2") (name "/GPIO11") (class "Default")
      (node (ref "R20") (pin "1") (pinfunction "1_1") (pintype "passive"))
      (node (ref "U1") (pin "50") (pinfunction "GPIO[11]_50") (pintype "passive"))
    )
    (net (code "3") (name "/SX1261_DIO3") (class "Default")
      (node (ref "P5") (pin "P$1") (pinfunction "P$1_P$1") (pintype "bidirectional"))
      (node (ref "U8") (pin "6") (pinfunction "DIO3_6") (pintype "bidirectional"))
    )
    (net (code "4") (name "/VR_PA") (class "Default")
      (node (ref "C26") (pin "1") (pinfunction "1_1") (pintype "passive"))
      (node (ref "C27") (pin "1") (pinfunction "1_1") (pintype "passive"))
      (node (ref "L7") (pin "2") (pinfunction "2_2") (pintype "passive"))
      (node (ref "U3") (pin "1") (pinfunction "VR_PA_1") (pintype "bidirectional"))
    )
    (net (code "5") (name "1V2") (class "Default")
      (node (ref "C76") (pin "2") (pinfunction "2_2") (pintype "passive"))
      (node (ref "C77") (pin "2") (pinfunction "2_2") (pintype "passive"))
      (node (ref "C78") (pin "2") (pinfunction "2_2") (pintype "passive"))
      (node (ref "FB3") (pin "1") (pinfunction "1_1") (pintype "passive"))
      (node (ref "L20") (pin "2") (pinfunction "2_2") (pintype "passive"))
      (node (ref "R49") (pin "1") (pinfunction "1_1") (pintype "passive"))
    )
    (net (code "6") (name "3V3_MAIN") (class "Default")
      (node (ref "C62") (pin "2") (pinfunction "2_2") (pintype "passive"))
      (node (ref "C64") (pin "2") (pinfunction "2_2") (pintype "passive"))
      (node (ref "C65") (pin "2") (pinfunction "2_2") (pintype "passive"))
      (node (ref "C68") (pin "2") (pinfunction "2_2") (pintype "passive"))
      (node (ref "C69") (pin "2") (pinfunction "2_2") (pintype "passive"))
      (node (ref "C71") (pin "2") (pinfunction "2_2") (pintype "passive"))
      (node (ref "C72") (pin "2") (pinfunction "2_2") (pintype "passive"))
      (node (ref "C73") (pin "2") (pinfunction "2_2") (pintype "passive"))
      (node (ref "C74") (pin "2") (pinfunction "2_2") (pintype "passive"))
      (node (ref "C75") (pin "2") (pinfunction "2_2") (pintype "passive"))
      (node (ref "FB5") (pin "1") (pinfunction "1_1") (pintype "passive"))
      (node (ref "FB6") (pin "1") (pinfunction "1_1") (pintype "passive"))
      (node (ref "J1") (pin "2") (pinfunction "3V3_2") (pintype "bidirectional"))
      (node (ref "J1") (pin "24") (pinfunction "3V3_24") (pintype "bidirectional"))
      (node (ref "J1") (pin "39") (pinfunction "3V3_39") (pintype "bidirectional"))
      (node (ref "J1") (pin "41") (pinfunction "3V3_41") (pintype "bidirectional"))
      (node (ref "J1") (pin "52") (pinfunction "3V3_52") (pintype "bidirectional"))
      (node (ref "P7") (pin "P$1") (pinfunction "P$1_P$1") (pintype "bidirectional"))
      (node (ref "Q1") (pin "2") (pinfunction "S_2") (pintype "passive"))
      (node (ref "R17") (pin "2") (pinfunction "2_2") (pintype "passive"))
      (node (ref "R44") (pin "2") (pinfunction "2_2") (pintype "passive"))
      (node (ref "R46") (pin "2") (pinfunction "2_2") (pintype "passive"))
      (node (ref "R47") (pin "2") (pinfunction "2_2") (pintype "passive"))
      (node (ref "R48") (pin "2") (pinfunction "2_2") (pintype "passive"))
      (node (ref "R51") (pin "1") (pinfunction "1_1") (pintype "passive"))
      (node (ref "R57") (pin "2") (pinfunction "2_2") (pintype "passive"))
      (node (ref "U10") (pin "3") (pinfunction "VDD_3") (pintype "bidirectional"))
      (node (ref "U11") (pin "1") (pinfunction "EN_1") (pintype "bidirectional"))
      (node (ref "U11") (pin "4") (pinfunction "VIN_4") (pintype "bidirectional"))
      (node (ref "U9") (pin "1") (pinfunction "VDD_1") (pintype "passive"))
      (node (ref "U9") (pin "17") (pinfunction "VDD_17") (pintype "power_in"))
      (node (ref "U9") (pin "5") (pinfunction "VDDA_5") (pintype "power_in"))
    )
    (net (code "7") (name "CONFIG_OK") (class "Default")
      (node (ref "R22") (pin "1") (pinfunction "1_1") (pintype "passive"))
      (node (ref "U1") (pin "66") (pinfunction "GPIO[0]_66") (pintype "passive"))
    )
    (net (code "8") (name "CSD") (class "Default")
      (node (ref "C51") (pin "1") (pinfunction "1_1") (pintype "passive"))
      (node (ref "R33") (pin "2") (pinfunction "2_2") (pintype "passive"))
      (node (ref "U6") (pin "4") (pinfunction "CSD_4") (pintype "input"))
    )
    (net (code "9") (name "D+") (class "Default")
      (node (ref "J1") (pin "38") (pinfunction "38_38") (pintype "bidirectional"))
      (node (ref "P2") (pin "P$1") (pinfunction "P$1_P$1") (pintype "bidirectional"))
      (node (ref "R9") (pin "1") (pinfunction "1_1") (pintype "passive"))
    )
    (net (code "10") (name "D-") (class "Default")
      (node (ref "J1") (pin "36") (pinfunction "36_36") (pintype "bidirectional"))
      (node (ref "P1") (pin "P$1") (pinfunction "P$1_P$1") (pintype "bidirectional"))
      (node (ref "R7") (pin "1") (pinfunction "1_1") (pintype "passive"))
    )
    (net (code "11") (name "GPIO6") (class "Default")
      (node (ref "U1") (pin "57") (pinfunction "GPIO[6]_57") (pintype "passive"))
    )
    (net (code "12") (name "GPIO9") (class "Default")
      (node (ref "U1") (pin "52") (pinfunction "GPIO[9]_52") (pintype "passive"))
    )
    (net (code "13") (name "HOST_CSN") (class "Default")
      (node (ref "P12") (pin "P$1") (pinfunction "P$1_P$1") (pintype "bidirectional"))
      (node (ref "R1") (pin "1") (pinfunction "1_1") (pintype "passive"))
      (node (ref "R13") (pin "1") (pinfunction "1_1") (pintype "passive"))
      (node (ref "U1") (pin "1") (pinfunction "HOST_CSN_1") (pintype "passive"))
      (node (ref "U9") (pin "10") (pinfunction "PA4_10") (pintype "bidirectional"))
    )
    (net (code "14") (name "HOST_MISO") (class "Default")
      (node (ref "P10") (pin "P$1") (pinfunction "P$1_P$1") (pintype "bidirectional"))
      (node (ref "R11") (pin "1") (pinfunction "1_1") (pintype "passive"))
      (node (ref "R2") (pin "2") (pinfunction "2_2") (pintype "passive"))
      (node (ref "R38") (pin "1") (pinfunction "1_1") (pintype "passive"))
      (node (ref "U9") (pin "12") (pinfunction "PA6_12") (pintype "bidirectional"))
    )
    (net (code "15") (name "HOST_MOSI") (class "Default")
      (node (ref "P11") (pin "P$1") (pinfunction "P$1_P$1") (pintype "bidirectional"))
      (node (ref "R12") (pin "1") (pinfunction "1_1") (pintype "passive"))
      (node (ref "U1") (pin "3") (pinfunction "HOST_MOSI_3") (pintype "passive"))
      (node (ref "U8") (pin "17") (pinfunction "MOSI_17") (pintype "bidirectional"))
      (node (ref "U9") (pin "13") (pinfunction "PA7_13") (pintype "bidirectional"))
    )
    (net (code "16") (name "HOST_SCK") (class "Default")
      (node (ref "P9") (pin "P$1") (pinfunction "P$1_P$1") (pintype "bidirectional"))
      (node (ref "R10") (pin "1") (pinfunction "1_1") (pintype "passive"))
      (node (ref "U1") (pin "4") (pinfunction "HOST_SCK_4") (pintype "passive"))
      (node (ref "U8") (pin "18") (pinfunction "SCK_18") (pintype "bidirectional"))
      (node (ref "U9") (pin "11") (pinfunction "PA5_11") (pintype "input"))
    )
    (net (code "17") (name "I2C_SCL") (class "Default")
      (node (ref "J1") (pin "30") (pinfunction "30_30") (pintype "bidirectional"))
      (node (ref "P16") (pin "P$1") (pinfunction "P$1_P$1") (pintype "bidirectional"))
      (node (ref "R47") (pin "1") (pinfunction "1_1") (pintype "passive"))
      (node (ref "U10") (pin "1") (pinfunction "SCL_1") (pintype "passive"))
      (node (ref "U9") (pin "29") (pinfunction "PB6_29") (pintype "bidirectional"))
    )
    (net (code "18") (name "I2C_SDA") (class "Default")
      (node (ref "J1") (pin "32") (pinfunction "32_32") (pintype "bidirectional"))
      (node (ref "P19") (pin "P$1") (pinfunction "P$1_P$1") (pintype "bidirectional"))
      (node (ref "R46") (pin "1") (pinfunction "1_1") (pintype "passive"))
      (node (ref "U10") (pin "6") (pinfunction "SDA_6") (pintype "bidirectional"))
      (node (ref "U9") (pin "30") (pinfunction "PB7_30") (pintype "bidirectional"))
    )
    (net (code "19") (name "MCU_NRESET") (class "Default")
      (node (ref "C80") (pin "2") (pinfunction "2_2") (pintype "passive"))
      (node (ref "P6") (pin "P$1") (pinfunction "P$1_P$1") (pintype "bidirectional"))
      (node (ref "R57") (pin "1") (pinfunction "1_1") (pintype "passive"))
      (node (ref "R58") (pin "1") (pinfunction "1_1") (pintype "passive"))
      (node (ref "U9") (pin "4") (pinfunction "NRST_4") (pintype "bidirectional"))
    )
    (net (code "20") (name "Net-(ANT1-SIGNAL)") (class "Default")
      (node (ref "ANT1") (pin "1") (pinfunction "SIGNAL_1") (pintype "bidirectional"))
      (node (ref "C47") (pin "1") (pinfunction "1_1") (pintype "passive"))
      (node (ref "D8") (pin "1") (pinfunction "1_1") (pintype "bidirectional"))
    )
    (net (code "21") (name "Net-(ANT2-SIGNAL)") (class "Default")
      (node (ref "ANT2") (pin "1") (pinfunction "SIGNAL_1") (pintype "bidirectional"))
      (node (ref "C50") (pin "1") (pinfunction "1_1") (pintype "passive"))
      (node (ref "D6") (pin "1") (pinfunction "1_1") (pintype "bidirectional"))
    )
    (net (code "22") (name "Net-(C15-Pad1)") (class "Default")
      (node (ref "C15") (pin "1") (pinfunction "1_1") (pintype "passive"))
      (node (ref "R26") (pin "1") (pinfunction "1_1") (pintype "passive"))
    )
    (net (code "23") (name "Net-(C21-Pad1)") (class "Default")
      (node (ref "C21") (pin "1") (pinfunction "1_1") (pintype "passive"))
      (node (ref "R28") (pin "1") (pinfunction "1_1") (pintype "passive"))
    )
    (net (code "24") (name "Net-(C28-Pad1)") (class "Default")
      (node (ref "C28") (pin "1") (pinfunction "1_1") (pintype "passive"))
      (node (ref "C29") (pin "1") (pinfunction "1_1") (pintype "passive"))
      (node (ref "C30") (pin "1") (pinfunction "1_1") (pintype "passive"))
      (node (ref "L8") (pin "2") (pinfunction "2_2") (pintype "passive"))
    )
    (net (code "25") (name "Net-(C30-Pad2)") (class "Default")
      (node (ref "C30") (pin "2") (pinfunction "2_2") (pintype "passive"))
      (node (ref "L9") (pin "1") (pinfunction "1_1") (pintype "passive"))
    )
    (net (code "26") (name "Net-(C40-Pad2)") (class "Default")
      (node (ref "C40") (pin "2") (pinfunction "2_2") (pintype "passive"))
      (node (ref "C41") (pin "2") (pinfunction "2_2") (pintype "passive"))
      (node (ref "L12") (pin "2") (pinfunction "2_2") (pintype "passive"))
      (node (ref "L13") (pin "1") (pinfunction "1_1") (pintype "passive"))
    )
    (net (code "27") (name "Net-(C44-Pad2)") (class "Default")
      (node (ref "C44") (pin "2") (pinfunction "2_2") (pintype "passive"))
      (node (ref "C45") (pin "1") (pinfunction "1_1") (pintype "passive"))
      (node (ref "L14") (pin "2") (pinfunction "2_2") (pintype "passive"))
      (node (ref "L15") (pin "1") (pinfunction "1_1") (pintype "passive"))
    )
    (net (code "28") (name "Net-(C46-Pad2)") (class "Default")
      (node (ref "C46") (pin "2") (pinfunction "2_2") (pintype "passive"))
      (node (ref "C47") (pin "2") (pinfunction "2_2") (pintype "passive"))
      (node (ref "L15") (pin "2") (pinfunction "2_2") (pintype "passive"))
    )
    (net (code "29") (name "Net-(C48-Pad2)") (class "Default")
      (node (ref "C48") (pin "2") (pinfunction "2_2") (pintype "passive"))
      (node (ref "L16") (pin "1") (pinfunction "1_1") (pintype "passive"))
      (node (ref "R32") (pin "2") (pinfunction "2_2") (pintype "passive"))
    )
    (net (code "30") (name "Net-(C49-Pad2)") (class "Default")
      (node (ref "C49") (pin "2") (pinfunction "2_2") (pintype "passive"))
      (node (ref "C50") (pin "2") (pinfunction "2_2") (pintype "passive"))
      (node (ref "L16") (pin "2") (pinfunction "2_2") (pintype "passive"))
    )
    (net (code "31") (name "Net-(C55-Pad1)") (class "Default")
      (node (ref "C55") (pin "1") (pinfunction "1_1") (pintype "passive"))
      (node (ref "R37") (pin "1") (pinfunction "1_1") (pintype "passive"))
    )
    (net (code "32") (name "Net-(C59-Pad1)") (class "Default")
      (node (ref "C59") (pin "1") (pinfunction "1_1") (pintype "passive"))
      (node (ref "C60") (pin "2") (pinfunction "2_2") (pintype "passive"))
      (node (ref "C61") (pin "2") (pinfunction "2_2") (pintype "passive"))
    )
    (net (code "33") (name "Net-(C63-Pad1)") (class "Default")
      (node (ref "C63") (pin "1") (pinfunction "1_1") (pintype "passive"))
      (node (ref "R54") (pin "1") (pinfunction "1_1") (pintype "passive"))
    )
    (net (code "34") (name "Net-(D1-+)") (class "Default")
      (node (ref "D1") (pin "1") (pinfunction "+_1") (pintype "passive"))
      (node (ref "R21") (pin "2") (pinfunction "2_2") (pintype "passive"))
    )
    (net (code "35") (name "Net-(D2-+)") (class "Default")
      (node (ref "D2") (pin "1") (pinfunction "+_1") (pintype "passive"))
      (node (ref "R22") (pin "2") (pinfunction "2_2") (pintype "passive"))
    )
    (net (code "36") (name "Net-(D3-+)") (class "Default")
      (node (ref "D3") (pin "1") (pinfunction "+_1") (pintype "passive"))
      (node (ref "R23") (pin "2") (pinfunction "2_2") (pintype "passive"))
    )
    (net (code "37") (name "Net-(D5-+)") (class "Default")
      (node (ref "D5") (pin "1") (pinfunction "+_1") (pintype "passive"))
      (node (ref "R51") (pin "2") (pinfunction "2_2") (pintype "passive"))
    )
    (net (code "38") (name "Net-(J1-Pad45)") (class "Default")
      (node (ref "J1") (pin "45") (pinfunction "45_45") (pintype "bidirectional"))
      (node (ref "R10") (pin "2") (pinfunction "2_2") (pintype "passive"))
    )
    (net (code "39") (name "Net-(J1-Pad47)") (class "Default")
      (node (ref "J1") (pin "47") (pinfunction "47_47") (pintype "bidirectional"))
      (node (ref "R11") (pin "2") (pinfunction "2_2") (pintype "passive"))
    )
    (net (code "40") (name "Net-(J1-Pad49)") (class "Default")
      (node (ref "J1") (pin "49") (pinfunction "49_49") (pintype "bidirectional"))
      (node (ref "R12") (pin "2") (pinfunction "2_2") (pintype "passive"))
    )
    (net (code "41") (name "Net-(J1-Pad51)") (class "Default")
      (node (ref "J1") (pin "51") (pinfunction "51_51") (pintype "bidirectional"))
      (node (ref "R13") (pin "2") (pinfunction "2_2") (pintype "passive"))
    )
    (net (code "42") (name "Net-(Q1-G)") (class "Default")
      (node (ref "Q1") (pin "1") (pinfunction "G_1") (pintype "passive"))
      (node (ref "Q2") (pin "3") (pinfunction "D_3") (pintype "passive"))
      (node (ref "R17") (pin "1") (pinfunction "1_1") (pintype "passive"))
    )
    (net (code "43") (name "Net-(Q2-G)") (class "Default")
      (node (ref "Q2") (pin "1") (pinfunction "G_1") (pintype "passive"))
      (node (ref "R18") (pin "1") (pinfunction "1_1") (pintype "passive"))
      (node (ref "R52") (pin "1") (pinfunction "1_1") (pintype "passive"))
    )
    (net (code "44") (name "Net-(U1-HOST_MISO)") (class "Default")
      (node (ref "R2") (pin "1") (pinfunction "1_1") (pintype "passive"))
      (node (ref "U1") (pin "2") (pinfunction "HOST_MISO_2") (pintype "passive"))
    )
    (net (code "45") (name "Net-(U1-RADIO_A_CLK_I)") (class "Default")
      (node (ref "R14") (pin "1") (pinfunction "1_1") (pintype "passive"))
      (node (ref "U1") (pin "43") (pinfunction "RADIO_A_CLK_I_43") (pintype "passive"))
    )
    (net (code "46") (name "Net-(U1-RADIO_B_CLK_I)") (class "Default")
      (node (ref "R8") (pin "1") (pinfunction "1_1") (pintype "passive"))
      (node (ref "U1") (pin "34") (pinfunction "RADIO_B_CLK_I_34") (pintype "passive"))
    )
    (net (code "47") (name "Net-(U2-DCC_SW)") (class "Default")
      (node (ref "L1") (pin "2") (pinfunction "2_2") (pintype "passive"))
      (node (ref "U2") (pin "8") (pinfunction "DCC_SW_8") (pintype "bidirectional"))
    )
    (net (code "48") (name "Net-(U2-RFI_N)") (class "Default")
      (node (ref "C19") (pin "2") (pinfunction "2_2") (pintype "passive"))
      (node (ref "L3") (pin "2") (pinfunction "2_2") (pintype "passive"))
      (node (ref "U2") (pin "23") (pinfunction "RFI_N_23") (pintype "bidirectional"))
    )
    (net (code "49") (name "Net-(U2-RFI_P)") (class "Default")
      (node (ref "C18") (pin "2") (pinfunction "2_2") (pintype "passive"))
      (node (ref "L3") (pin "1") (pinfunction "1_1") (pintype "passive"))
      (node (ref "U2") (pin "22") (pinfunction "RFI_P_22") (pintype "bidirectional"))
    )
    (net (code "50") (name "Net-(U2-VDD_IN)") (class "Default")
      (node (ref "C14") (pin "1") (pinfunction "1_1") (pintype "passive"))
      (node (ref "L2") (pin "2") (pinfunction "2_2") (pintype "passive"))
      (node (ref "R25") (pin "1") (pinfunction "1_1") (pintype "passive"))
      (node (ref "U2") (pin "2") (pinfunction "VDD_IN_2") (pintype "bidirectional"))
    )
    (net (code "51") (name "Net-(U2-VREG)") (class "Default")
      (node (ref "C16") (pin "1") (pinfunction "1_1") (pintype "passive"))
      (node (ref "L1") (pin "1") (pinfunction "1_1") (pintype "passive"))
      (node (ref "L2") (pin "1") (pinfunction "1_1") (pintype "passive"))
      (node (ref "U2") (pin "6") (pinfunction "VREG_6") (pintype "bidirectional"))
    )
    (net (code "52") (name "Net-(U2-XTA)") (class "Default")
      (node (ref "C15") (pin "2") (pinfunction "2_2") (pintype "passive"))
      (node (ref "U2") (pin "3") (pinfunction "XTA_3") (pintype "bidirectional"))
    )
    (net (code "53") (name "Net-(U3-DCC_SW)") (class "Default")
      (node (ref "L4") (pin "2") (pinfunction "2_2") (pintype "passive"))
      (node (ref "U3") (pin "8") (pinfunction "DCC_SW_8") (pintype "bidirectional"))
    )
    (net (code "54") (name "Net-(U3-RFI_N)") (class "Default")
      (node (ref "C25") (pin "2") (pinfunction "2_2") (pintype "passive"))
      (node (ref "L6") (pin "2") (pinfunction "2_2") (pintype "passive"))
      (node (ref "U3") (pin "23") (pinfunction "RFI_N_23") (pintype "bidirectional"))
    )
    (net (code "55") (name "Net-(U3-RFI_P)") (class "Default")
      (node (ref "C24") (pin "2") (pinfunction "2_2") (pintype "passive"))
      (node (ref "L6") (pin "1") (pinfunction "1_1") (pintype "passive"))
      (node (ref "U3") (pin "22") (pinfunction "RFI_P_22") (pintype "bidirectional"))
    )
    (net (code "56") (name "Net-(U3-RFO)") (class "Default")
      (node (ref "C28") (pin "2") (pinfunction "2_2") (pintype "passive"))
      (node (ref "L7") (pin "1") (pinfunction "1_1") (pintype "passive"))
      (node (ref "L8") (pin "1") (pinfunction "1_1") (pintype "passive"))
      (node (ref "U3") (pin "24") (pinfunction "RFO_24") (pintype "bidirectional"))
    )
    (net (code "57") (name "Net-(U3-VDD_IN)") (class "Default")
      (node (ref "C20") (pin "1") (pinfunction "1_1") (pintype "passive"))
      (node (ref "L5") (pin "2") (pinfunction "2_2") (pintype "passive"))
      (node (ref "R27") (pin "1") (pinfunction "1_1") (pintype "passive"))
      (node (ref "U3") (pin "2") (pinfunction "VDD_IN_2") (pintype "bidirectional"))
    )
    (net (code "58") (name "Net-(U3-VREG)") (class "Default")
      (node (ref "C22") (pin "1") (pinfunction "1_1") (pintype "passive"))
      (node (ref "L4") (pin "1") (pinfunction "1_1") (pintype "passive"))
      (node (ref "L5") (pin "1") (pinfunction "1_1") (pintype "passive"))
      (node (ref "U3") (pin "6") (pinfunction "VREG_6") (pintype "bidirectional"))
    )
    (net (code "59") (name "Net-(U3-XTA)") (class "Default")
      (node (ref "C21") (pin "2") (pinfunction "2_2") (pintype "passive"))
      (node (ref "U3") (pin "3") (pinfunction "XTA_3") (pintype "bidirectional"))
    )
    (net (code "60") (name "Net-(U4-IN{slash}OUT)") (class "Default")
      (node (ref "C34") (pin "1") (pinfunction "1_1") (pintype "passive"))
      (node (ref "U4") (pin "2") (pinfunction "IN/OUT_2") (pintype "bidirectional"))
    )
    (net (code "61") (name "Net-(U4-OUT{slash}IN)") (class "Default")
      (node (ref "C19") (pin "1") (pinfunction "1_1") (pintype "passive"))
      (node (ref "C25") (pin "1") (pinfunction "1_1") (pintype "passive"))
      (node (ref "C61") (pin "1") (pinfunction "1_1") (pintype "passive"))
      (node (ref "U4") (pin "5") (pinfunction "OUT/IN_5") (pintype "bidirectional"))
    )
    (net (code "62") (name "Net-(U5-IN{slash}OUT)") (class "Default")
      (node (ref "R31") (pin "2") (pinfunction "2_2") (pintype "passive"))
      (node (ref "R32") (pin "1") (pinfunction "1_1") (pintype "passive"))
      (node (ref "U5") (pin "2") (pinfunction "IN/OUT_2") (pintype "bidirectional"))
    )
    (net (code "63") (name "Net-(U5-OUT{slash}IN)") (class "Default")
      (node (ref "U5") (pin "5") (pinfunction "OUT/IN_5") (pintype "bidirectional"))
      (node (ref "U6") (pin "7") (pinfunction "LNA_IN_7") (pintype "passive"))
    )
    (net (code "64") (name "Net-(U6-ANT)") (class "Default")
      (node (ref "C43") (pin "2") (pinfunction "2_2") (pintype "passive"))
      (node (ref "C45") (pin "2") (pinfunction "2_2") (pintype "passive"))
      (node (ref "L14") (pin "1") (pinfunction "1_1") (pintype "passive"))
      (node (ref "U6") (pin "9") (pinfunction "ANT_9") (pintype "passive"))
    )
    (net (code "65") (name "Net-(U6-PA_OUT)") (class "Default")
      (node (ref "L11") (pin "1") (pinfunction "1_1") (pintype "passive"))
      (node (ref "L12") (pin "1") (pinfunction "1_1") (pintype "passive"))
      (node (ref "U6") (pin "13") (pinfunction "PA_OUT_13") (pintype "passive"))
    )
    (net (code "66") (name "Net-(U6-RX)") (class "Default")
      (node (ref "C34") (pin "2") (pinfunction "2_2") (pintype "passive"))
      (node (ref "U6") (pin "2") (pinfunction "RX_2") (pintype "passive"))
    )
    (net (code "67") (name "Net-(U6-RX_FLT)") (class "Default")
      (node (ref "R31") (pin "1") (pinfunction "1_1") (pintype "passive"))
      (node (ref "U6") (pin "8") (pinfunction "RX_FLT_8") (pintype "passive"))
    )
    (net (code "68") (name "Net-(U6-TX)") (class "Default")
      (node (ref "C33") (pin "2") (pinfunction "2_2") (pintype "passive"))
      (node (ref "U6") (pin "1") (pinfunction "TX_1") (pintype "passive"))
    )
    (net (code "69") (name "Net-(U6-TX_IN)") (class "Default")
      (node (ref "C42") (pin "2") (pinfunction "2_2") (pintype "passive"))
      (node (ref "L13") (pin "2") (pinfunction "2_2") (pintype "passive"))
      (node (ref "U6") (pin "11") (pinfunction "TX_IN_11") (pintype "passive"))
    )
    (net (code "70") (name "Net-(U6-VCC1)") (class "Default")
      (node (ref "L10") (pin "1") (pinfunction "1_1") (pintype "passive"))
      (node (ref "U6") (pin "16") (pinfunction "VCC1_16") (pintype "power_in"))
    )
    (net (code "71") (name "Net-(U8-DCC_SW)") (class "Default")
      (node (ref "L18") (pin "2") (pinfunction "2_2") (pintype "passive"))
      (node (ref "U8") (pin "9") (pinfunction "DCC_SW_9") (pintype "bidirectional"))
    )
    (net (code "72") (name "Net-(U8-MISO)") (class "Default")
      (node (ref "R38") (pin "2") (pinfunction "2_2") (pintype "passive"))
      (node (ref "U8") (pin "16") (pinfunction "MISO_16") (pintype "bidirectional"))
    )
    (net (code "73") (name "Net-(U8-NSS)") (class "Default")
      (node (ref "R41") (pin "2") (pinfunction "2_2") (pintype "passive"))
      (node (ref "U8") (pin "19") (pinfunction "NSS_19") (pintype "bidirectional"))
    )
    (net (code "74") (name "Net-(U8-RFI_N)") (class "Default")
      (node (ref "C59") (pin "2") (pinfunction "2_2") (pintype "passive"))
      (node (ref "L19") (pin "2") (pinfunction "2_2") (pintype "passive"))
      (node (ref "U8") (pin "22") (pinfunction "RFI_N_22") (pintype "bidirectional"))
    )
    (net (code "75") (name "Net-(U8-RFI_P)") (class "Default")
      (node (ref "C58") (pin "2") (pinfunction "2_2") (pintype "passive"))
      (node (ref "L19") (pin "1") (pinfunction "1_1") (pintype "passive"))
      (node (ref "U8") (pin "21") (pinfunction "RFI_P_21") (pintype "bidirectional"))
    )
    (net (code "76") (name "Net-(U8-VDD_IN)") (class "Default")
      (node (ref "C54") (pin "1") (pinfunction "1_1") (pintype "passive"))
      (node (ref "L17") (pin "2") (pinfunction "2_2") (pintype "passive"))
      (node (ref "R36") (pin "1") (pinfunction "1_1") (pintype "passive"))
      (node (ref "U8") (pin "1") (pinfunction "VDD_IN_1") (pintype "bidirectional"))
    )
    (net (code "77") (name "Net-(U8-VREG)") (class "Default")
      (node (ref "C56") (pin "1") (pinfunction "1_1") (pintype "passive"))
      (node (ref "L17") (pin "1") (pinfunction "1_1") (pintype "passive"))
      (node (ref "L18") (pin "1") (pinfunction "1_1") (pintype "passive"))
      (node (ref "U8") (pin "7") (pinfunction "VREG_7") (pintype "bidirectional"))
    )
    (net (code "78") (name "Net-(U8-XTA)") (class "Default")
      (node (ref "C55") (pin "2") (pinfunction "2_2") (pintype "passive"))
      (node (ref "U8") (pin "3") (pinfunction "XTA_3") (pintype "bidirectional"))
    )
    (net (code "79") (name "Net-(U9-BOOT)") (class "Default")
      (node (ref "R44") (pin "1") (pinfunction "1_1") (pintype "passive"))
      (node (ref "R45") (pin "2") (pinfunction "2_2") (pintype "passive"))
      (node (ref "U9") (pin "31") (pinfunction "BOOT_31") (pintype "bidirectional"))
    )
    (net (code "80") (name "Net-(U9-PA0-CK_IN)") (class "Default")
      (node (ref "R42") (pin "2") (pinfunction "2_2") (pintype "passive"))
      (node (ref "R43") (pin "1") (pinfunction "1_1") (pintype "passive"))
      (node (ref "U9") (pin "6") (pinfunction "PA0-CK_IN_6") (pintype "bidirectional"))
    )
    (net (code "81") (name "Net-(U9-PC14-OSC32_IN)") (class "Default")
      (node (ref "C66") (pin "2") (pinfunction "2_2") (pintype "passive"))
      (node (ref "U9") (pin "2") (pinfunction "PC14-OSC32_IN_2") (pintype "bidirectional"))
      (node (ref "Y1") (pin "2") (pinfunction "2_2") (pintype "bidirectional"))
    )
    (net (code "82") (name "Net-(U9-PC15-OSC32_OUT)") (class "Default")
      (node (ref "C67") (pin "1") (pinfunction "1_1") (pintype "passive"))
      (node (ref "U9") (pin "3") (pinfunction "PC15-OSC32_OUT_3") (pintype "bidirectional"))
      (node (ref "Y1") (pin "1") (pinfunction "1_1") (pintype "bidirectional"))
    )
    (net (code "83") (name "Net-(U10-\\E\\V\\E\\N\\T\\)") (class "Default")
      (node (ref "R48") (pin "1") (pinfunction "1_1") (pintype "passive"))
      (node (ref "U10") (pin "2") (pinfunction "\\E\\V\\E\\N\\T\\_2") (pintype "passive"))
    )
    (net (code "84") (name "Net-(U11-FB)") (class "Default")
      (node (ref "R49") (pin "2") (pinfunction "2_2") (pintype "passive"))
      (node (ref "R50") (pin "1") (pinfunction "1_1") (pintype "passive"))
      (node (ref "U11") (pin "5") (pinfunction "FB_5") (pintype "bidirectional"))
    )
    (net (code "85") (name "Net-(U11-SW)") (class "Default")
      (node (ref "L20") (pin "1") (pinfunction "1_1") (pintype "passive"))
      (node (ref "U11") (pin "3") (pinfunction "SW_3") (pintype "bidirectional"))
    )
    (net (code "86") (name "Net-(U12-IN{slash}OUT)") (class "Default")
      (node (ref "C31") (pin "1") (pinfunction "1_1") (pintype "passive"))
      (node (ref "L9") (pin "2") (pinfunction "2_2") (pintype "passive"))
      (node (ref "U12") (pin "2") (pinfunction "IN/OUT_2") (pintype "bidirectional"))
    )
    (net (code "87") (name "Net-(U12-OUT{slash}IN)") (class "Default")
      (node (ref "C33") (pin "1") (pinfunction "1_1") (pintype "passive"))
      (node (ref "U12") (pin "5") (pinfunction "OUT/IN_5") (pintype "bidirectional"))
    )
    (net (code "88") (name "Net-(Y2-OUT)") (class "Default")
      (node (ref "R24") (pin "1") (pinfunction "1_1") (pintype "passive"))
      (node (ref "Y2") (pin "3") (pinfunction "OUT_3") (pintype "bidirectional"))
    )
    (net (code "89") (name "Net-(Y2-VCC)") (class "Default")
      (node (ref "C13") (pin "2") (pinfunction "2_2") (pintype "passive"))
      (node (ref "FB1") (pin "2") (pinfunction "2_2") (pintype "passive"))
      (node (ref "Y2") (pin "4") (pinfunction "VCC_4") (pintype "bidirectional"))
    )
    (net (code "90") (name "PA_ON") (class "Default")
      (node (ref "C53") (pin "1") (pinfunction "1_1") (pintype "passive"))
      (node (ref "R35") (pin "2") (pinfunction "2_2") (pintype "passive"))
      (node (ref "U6") (pin "5") (pinfunction "CPS_5") (pintype "input"))
    )
    (net (code "91") (name "POWER_EN") (class "Default")
      (node (ref "U9") (pin "7") (pinfunction "PA1_7") (pintype "bidirectional"))
    )
    (net (code "92") (name "POWER_GND") (class "Default")
      (node (ref "ANT1") (pin "2") (pinfunction "GND_2") (pintype "bidirectional"))
      (node (ref "ANT1") (pin "3") (pinfunction "GND_3") (pintype "bidirectional"))
      (node (ref "ANT2") (pin "2") (pinfunction "GND_2") (pintype "bidirectional"))
      (node (ref "ANT2") (pin "3") (pinfunction "GND_3") (pintype "bidirectional"))
      (node (ref "C1") (pin "1") (pinfunction "1_1") (pintype "passive"))
      (node (ref "C10") (pin "1") (pinfunction "1_1") (pintype "passive"))
      (node (ref "C11") (pin "1") (pinfunction "1_1") (pintype "passive"))
      (node (ref "C12") (pin "1") (pinfunction "1_1") (pintype "passive"))
      (node (ref "C13") (pin "1") (pinfunction "1_1") (pintype "passive"))
      (node (ref "C14") (pin "2") (pinfunction "2_2") (pintype "passive"))
      (node (ref "C16") (pin "2") (pinfunction "2_2") (pintype "passive"))
      (node (ref "C17") (pin "1") (pinfunction "1_1") (pintype "passive"))
      (node (ref "C18") (pin "1") (pinfunction "1_1") (pintype "passive"))
      (node (ref "C2") (pin "1") (pinfunction "1_1") (pintype "passive"))
      (node (ref "C20") (pin "2") (pinfunction "2_2") (pintype "passive"))
      (node (ref "C22") (pin "2") (pinfunction "2_2") (pintype "passive"))
      (node (ref "C23") (pin "1") (pinfunction "1_1") (pintype "passive"))
      (node (ref "C24") (pin "1") (pinfunction "1_1") (pintype "passive"))
      (node (ref "C26") (pin "2") (pinfunction "2_2") (pintype "passive"))
      (node (ref "C27") (pin "2") (pinfunction "2_2") (pintype "passive"))
      (node (ref "C29") (pin "2") (pinfunction "2_2") (pintype "passive"))
      (node (ref "C3") (pin "1") (pinfunction "1_1") (pintype "passive"))
      (node (ref "C31") (pin "2") (pinfunction "2_2") (pintype "passive"))
      (node (ref "C35") (pin "1") (pinfunction "1_1") (pintype "passive"))
      (node (ref "C36") (pin "1") (pinfunction "1_1") (pintype "passive"))
      (node (ref "C37") (pin "1") (pinfunction "1_1") (pintype "passive"))
      (node (ref "C38") (pin "1") (pinfunction "1_1") (pintype "passive"))
      (node (ref "C39") (pin "1") (pinfunction "1_1") (pintype "passive"))
      (node (ref "C4") (pin "1") (pinfunction "1_1") (pintype "passive"))
      (node (ref "C40") (pin "1") (pinfunction "1_1") (pintype "passive"))
      (node (ref "C41") (pin "1") (pinfunction "1_1") (pintype "passive"))
      (node (ref "C42") (pin "1") (pinfunction "1_1") (pintype "passive"))
      (node (ref "C43") (pin "1") (pinfunction "1_1") (pintype "passive"))
      (node (ref "C44") (pin "1") (pinfunction "1_1") (pintype "passive"))
      (node (ref "C46") (pin "1") (pinfunction "1_1") (pintype "passive"))
      (node (ref "C48") (pin "1") (pinfunction "1_1") (pintype "passive"))
      (node (ref "C49") (pin "1") (pinfunction "1_1") (pintype "passive"))
      (node (ref "C5") (pin "1") (pinfunction "1_1") (pintype "passive"))
      (node (ref "C51") (pin "2") (pinfunction "2_2") (pintype "passive"))
      (node (ref "C52") (pin "2") (pinfunction "2_2") (pintype "passive"))
      (node (ref "C53") (pin "2") (pinfunction "2_2") (pintype "passive"))
      (node (ref "C54") (pin "2") (pinfunction "2_2") (pintype "passive"))
      (node (ref "C56") (pin "2") (pinfunction "2_2") (pintype "passive"))
      (node (ref "C57") (pin "1") (pinfunction "1_1") (pintype "passive"))
      (node (ref "C58") (pin "1") (pinfunction "1_1") (pintype "passive"))
      (node (ref "C6") (pin "1") (pinfunction "1_1") (pintype "passive"))
      (node (ref "C60") (pin "1") (pinfunction "1_1") (pintype "passive"))
      (node (ref "C62") (pin "1") (pinfunction "1_1") (pintype "passive"))
      (node (ref "C64") (pin "1") (pinfunction "1_1") (pintype "passive"))
      (node (ref "C65") (pin "1") (pinfunction "1_1") (pintype "passive"))
      (node (ref "C66") (pin "1") (pinfunction "1_1") (pintype "passive"))
      (node (ref "C67") (pin "2") (pinfunction "2_2") (pintype "passive"))
      (node (ref "C68") (pin "1") (pinfunction "1_1") (pintype "passive"))
      (node (ref "C69") (pin "1") (pinfunction "1_1") (pintype "passive"))
      (node (ref "C7") (pin "1") (pinfunction "1_1") (pintype "passive"))
      (node (ref "C71") (pin "1") (pinfunction "1_1") (pintype "passive"))
      (node (ref "C72") (pin "1") (pinfunction "1_1") (pintype "passive"))
      (node (ref "C73") (pin "1") (pinfunction "1_1") (pintype "passive"))
      (node (ref "C74") (pin "1") (pinfunction "1_1") (pintype "passive"))
      (node (ref "C75") (pin "1") (pinfunction "1_1") (pintype "passive"))
      (node (ref "C76") (pin "1") (pinfunction "1_1") (pintype "passive"))
      (node (ref "C77") (pin "1") (pinfunction "1_1") (pintype "passive"))
      (node (ref "C78") (pin "1") (pinfunction "1_1") (pintype "passive"))
      (node (ref "C79") (pin "1") (pinfunction "1_1") (pintype "passive"))
      (node (ref "C8") (pin "1") (pinfunction "1_1") (pintype "passive"))
      (node (ref "C80") (pin "1") (pinfunction "1_1") (pintype "passive"))
      (node (ref "C81") (pin "1") (pinfunction "1_1") (pintype "passive"))
      (node (ref "C82") (pin "1") (pinfunction "1_1") (pintype "passive"))
      (node (ref "C83") (pin "1") (pinfunction "1_1") (pintype "passive"))
      (node (ref "C84") (pin "1") (pinfunction "1_1") (pintype "passive"))
      (node (ref "C9") (pin "1") (pinfunction "1_1") (pintype "passive"))
      (node (ref "D1") (pin "2") (pinfunction "-_2") (pintype "passive"))
      (node (ref "D2") (pin "2") (pinfunction "-_2") (pintype "passive"))
      (node (ref "D3") (pin "2") (pinfunction "-_2") (pintype "passive"))
      (node (ref "D5") (pin "2") (pinfunction "-_2") (pintype "passive"))
      (node (ref "D6") (pin "2") (pinfunction "2_2") (pintype "bidirectional"))
      (node (ref "D8") (pin "2") (pinfunction "2_2") (pintype "bidirectional"))
      (node (ref "J1") (pin "15") (pinfunction "GND_15") (pintype "bidirectional"))
      (node (ref "J1") (pin "18") (pinfunction "GND_18") (pintype "bidirectional"))
      (node (ref "J1") (pin "21") (pinfunction "GND_21") (pintype "bidirectional"))
      (node (ref "J1") (pin "26") (pinfunction "GND_26") (pintype "bidirectional"))
      (node (ref "J1") (pin "27") (pinfunction "GND_27") (pintype "bidirectional"))
      (node (ref "J1") (pin "29") (pinfunction "GND_29") (pintype "bidirectional"))
      (node (ref "J1") (pin "34") (pinfunction "GND_34") (pintype "bidirectional"))
      (node (ref "J1") (pin "35") (pinfunction "GND_35") (pintype "bidirectional"))
      (node (ref "J1") (pin "37") (pinfunction "GND_37") (pintype "bidirectional"))
      (node (ref "J1") (pin "4") (pinfunction "GND_4") (pintype "bidirectional"))
      (node (ref "J1") (pin "40") (pinfunction "GND_40") (pintype "bidirectional"))
      (node (ref "J1") (pin "43") (pinfunction "GND_43") (pintype "bidirectional"))
      (node (ref "J1") (pin "50") (pinfunction "GND_50") (pintype "bidirectional"))
      (node (ref "J1") (pin "9") (pinfunction "GND_9") (pintype "bidirectional"))
      (node (ref "J10") (pin "1") (pinfunction "1_1") (pintype "bidirectional"))
      (node (ref "J10") (pin "2") (pinfunction "2_2") (pintype "bidirectional"))
      (node (ref "J10") (pin "3") (pinfunction "3_3") (pintype "bidirectional"))
      (node (ref "J11") (pin "1") (pinfunction "P$1_1") (pintype "bidirectional"))
      (node (ref "J17") (pin "1") (pinfunction "1_1") (pintype "bidirectional"))
      (node (ref "J17") (pin "2") (pinfunction "2_2") (pintype "bidirectional"))
      (node (ref "J17") (pin "3") (pinfunction "3_3") (pintype "bidirectional"))
      (node (ref "J2") (pin "1") (pinfunction "P$1_1") (pintype "bidirectional"))
      (node (ref "J3") (pin "1") (pinfunction "1_1") (pintype "bidirectional"))
      (node (ref "J3") (pin "2") (pinfunction "2_2") (pintype "bidirectional"))
      (node (ref "J3") (pin "3") (pinfunction "3_3") (pintype "bidirectional"))
      (node (ref "J4") (pin "1") (pinfunction "1_1") (pintype "bidirectional"))
      (node (ref "J4") (pin "2") (pinfunction "2_2") (pintype "bidirectional"))
      (node (ref "J4") (pin "3") (pinfunction "3_3") (pintype "bidirectional"))
      (node (ref "J5") (pin "1") (pinfunction "1_1") (pintype "bidirectional"))
      (node (ref "J5") (pin "2") (pinfunction "2_2") (pintype "bidirectional"))
      (node (ref "J5") (pin "3") (pinfunction "3_3") (pintype "bidirectional"))
      (node (ref "J6") (pin "1") (pinfunction "1_1") (pintype "bidirectional"))
      (node (ref "J6") (pin "2") (pinfunction "2_2") (pintype "bidirectional"))
      (node (ref "J6") (pin "3") (pinfunction "3_3") (pintype "bidirectional"))
      (node (ref "J7") (pin "1") (pinfunction "1_1") (pintype "bidirectional"))
      (node (ref "J7") (pin "2") (pinfunction "2_2") (pintype "bidirectional"))
      (node (ref "J7") (pin "3") (pinfunction "3_3") (pintype "bidirectional"))
      (node (ref "P24") (pin "P$1") (pinfunction "P$1_P$1") (pintype "bidirectional"))
      (node (ref "P8") (pin "P$1") (pinfunction "P$1_P$1") (pintype "bidirectional"))
      (node (ref "Q2") (pin "2") (pinfunction "S_2") (pintype "passive"))
      (node (ref "R15") (pin "1") (pinfunction "1_1") (pintype "passive"))
      (node (ref "R15") (pin "2") (pinfunction "2_2") (pintype "passive"))
      (node (ref "R16") (pin "1") (pinfunction "1_1") (pintype "passive"))
      (node (ref "R16") (pin "2") (pinfunction "2_2") (pintype "passive"))
      (node (ref "R3") (pin "1") (pinfunction "1_1") (pintype "passive"))
      (node (ref "R3") (pin "2") (pinfunction "2_2") (pintype "passive"))
      (node (ref "R43") (pin "2") (pinfunction "2_2") (pintype "passive"))
      (node (ref "R45") (pin "1") (pinfunction "1_1") (pintype "passive"))
      (node (ref "R5") (pin "1") (pinfunction "1_1") (pintype "passive"))
      (node (ref "R50") (pin "2") (pinfunction "2_2") (pintype "passive"))
      (node (ref "R52") (pin "2") (pinfunction "2_2") (pintype "passive"))
      (node (ref "R53") (pin "1") (pinfunction "1_1") (pintype "passive"))
      (node (ref "R53") (pin "2") (pinfunction "2_2") (pintype "passive"))
      (node (ref "U1") (pin "15") (pinfunction "GND_15") (pintype "power_in"))
      (node (ref "U1") (pin "20") (pinfunction "SP_VALID_20") (pintype "passive"))
      (node (ref "U1") (pin "24") (pinfunction "GND_24") (pintype "power_in"))
      (node (ref "U1") (pin "25") (pinfunction "GND_25") (pintype "power_in"))
      (node (ref "U1") (pin "39") (pinfunction "GND_39") (pintype "power_in"))
      (node (ref "U1") (pin "46") (pinfunction "GND_46") (pintype "power_in"))
      (node (ref "U1") (pin "55") (pinfunction "GND_55") (pintype "power_in"))
      (node (ref "U1") (pin "6") (pinfunction "GND_6") (pintype "power_in"))
      (node (ref "U1") (pin "62") (pinfunction "GND_62") (pintype "power_in"))
      (node (ref "U1") (pin "69") (pinfunction "GND_69") (pintype "power_in"))
      (node (ref "U1") (pin "9") (pinfunction "GND_9") (pintype "passive"))
      (node (ref "U10") (pin "4") (pinfunction "ADDR/T\\H\\E\\R\\M\\_4") (pintype "passive"))
      (node (ref "U10") (pin "5") (pinfunction "GND_5") (pintype "bidirectional"))
      (node (ref "U11") (pin "2") (pinfunction "GND_2") (pintype "bidirectional"))
      (node (ref "U12") (pin "1") (pinfunction "GND_1") (pintype "bidirectional"))
      (node (ref "U12") (pin "3") (pinfunction "GND_3") (pintype "bidirectional"))
      (node (ref "U12") (pin "4") (pinfunction "GND_4") (pintype "bidirectional"))
      (node (ref "U12") (pin "6") (pinfunction "GND_6") (pintype "bidirectional"))
      (node (ref "U2") (pin "20") (pinfunction "GND_20") (pintype "bidirectional"))
      (node (ref "U2") (pin "25") (pinfunction "GND_25") (pintype "power_in"))
      (node (ref "U2") (pin "7") (pinfunction "GND_7") (pintype "power_in"))
      (node (ref "U3") (pin "20") (pinfunction "GND_20") (pintype "bidirectional"))
      (node (ref "U3") (pin "25") (pinfunction "GND_25") (pintype "power_in"))
      (node (ref "U3") (pin "7") (pinfunction "GND_7") (pintype "power_in"))
      (node (ref "U4") (pin "1") (pinfunction "GND_1") (pintype "bidirectional"))
      (node (ref "U4") (pin "3") (pinfunction "GND_3") (pintype "bidirectional"))
      (node (ref "U4") (pin "4") (pinfunction "GND_4") (pintype "bidirectional"))
      (node (ref "U4") (pin "6") (pinfunction "GND_6") (pintype "bidirectional"))
      (node (ref "U5") (pin "1") (pinfunction "GND_1") (pintype "bidirectional"))
      (node (ref "U5") (pin "3") (pinfunction "GND_3") (pintype "bidirectional"))
      (node (ref "U5") (pin "4") (pinfunction "GND_4") (pintype "bidirectional"))
      (node (ref "U5") (pin "6") (pinfunction "GND_6") (pintype "bidirectional"))
      (node (ref "U6") (pin "10") (pinfunction "GND_10") (pintype "power_in"))
      (node (ref "U6") (pin "12") (pinfunction "GND_12") (pintype "power_in"))
      (node (ref "U6") (pin "17") (pinfunction "GND_17") (pintype "power_in"))
      (node (ref "U8") (pin "2") (pinfunction "GND_2") (pintype "bidirectional"))
      (node (ref "U8") (pin "20") (pinfunction "GND_20") (pintype "bidirectional"))
      (node (ref "U8") (pin "25") (pinfunction "GND_25") (pintype "bidirectional"))
      (node (ref "U8") (pin "5") (pinfunction "GND_5") (pintype "bidirectional"))
      (node (ref "U8") (pin "8") (pinfunction "GND_8") (pintype "bidirectional"))
      (node (ref "U9") (pin "16") (pinfunction "VSS_16") (pintype "power_in"))
      (node (ref "U9") (pin "32") (pinfunction "VSS_32") (pintype "power_in"))
      (node (ref "U9") (pin "33") (pinfunction "VSS_33") (pintype "power_in"))
      (node (ref "Y2") (pin "1") (pinfunction "GND_1") (pintype "bidirectional"))
      (node (ref "Y2") (pin "2") (pinfunction "GND_2") (pintype "bidirectional"))
    )
    (net (code "93") (name "PPS") (class "Default")
      (node (ref "J1") (pin "19") (pinfunction "19_19") (pintype "bidirectional"))
      (node (ref "P21") (pin "P$1") (pinfunction "P$1_P$1") (pintype "bidirectional"))
      (node (ref "U1") (pin "8") (pinfunction "PPS_8") (pintype "passive"))
      (node (ref "U9") (pin "27") (pinfunction "PB4_27") (pintype "bidirectional"))
    )
    (net (code "94") (name "P_RESET") (class "Default")
      (node (ref "D4") (pin "+") (pinfunction "+_+") (pintype "passive"))
      (node (ref "J1") (pin "22") (pinfunction "22_22") (pintype "bidirectional"))
      (node (ref "P20") (pin "P$1") (pinfunction "P$1_P$1") (pintype "bidirectional"))
      (node (ref "R58") (pin "2") (pinfunction "2_2") (pintype "passive"))
    )
    (net (code "95") (name "RADIO_A_CLK_32M") (class "Default")
      (node (ref "R14") (pin "2") (pinfunction "2_2") (pintype "passive"))
      (node (ref "R42") (pin "1") (pinfunction "1_1") (pintype "passive"))
      (node (ref "U3") (pin "14") (pinfunction "BUSY_14") (pintype "bidirectional"))
    )
    (net (code "96") (name "RADIO_A_CLK_O") (class "Default")
      (node (ref "U1") (pin "48") (pinfunction "RADIO_A_IQ[4]_48") (pintype "passive"))
      (node (ref "U3") (pin "11") (pinfunction "DIO5_11") (pintype "bidirectional"))
    )
    (net (code "97") (name "RADIO_A_CSN") (class "Default")
      (node (ref "U1") (pin "68") (pinfunction "RADIO_A_CSN_68") (pintype "passive"))
      (node (ref "U3") (pin "19") (pinfunction "NSS_19") (pintype "bidirectional"))
    )
    (net (code "98") (name "RADIO_A_IQ0") (class "Default")
      (node (ref "U1") (pin "44") (pinfunction "RADIO_A_IQ[0]_44") (pintype "passive"))
      (node (ref "U3") (pin "13") (pinfunction "DIO1_13") (pintype "bidirectional"))
    )
    (net (code "99") (name "RADIO_A_IQ1") (class "Default")
      (node (ref "U1") (pin "45") (pinfunction "RADIO_A_IQ[1]_45") (pintype "passive"))
      (node (ref "U3") (pin "12") (pinfunction "DIO2_12") (pintype "bidirectional"))
    )
    (net (code "100") (name "RADIO_A_IQ2") (class "Default")
      (node (ref "U1") (pin "49") (pinfunction "RADIO_A_IQ[2]_49") (pintype "passive"))
      (node (ref "U3") (pin "5") (pinfunction "DIO3_5") (pintype "bidirectional"))
    )
    (net (code "101") (name "RADIO_A_IQ3") (class "Default")
      (node (ref "U1") (pin "41") (pinfunction "RADIO_A_IQ[3]_41") (pintype "passive"))
      (node (ref "U3") (pin "21") (pinfunction "DIO4_21") (pintype "bidirectional"))
    )
    (net (code "102") (name "RADIO_A_MISO") (class "Default")
      (node (ref "U1") (pin "42") (pinfunction "RADIO_A_MISO_42") (pintype "passive"))
      (node (ref "U3") (pin "16") (pinfunction "MISO_TX_16") (pintype "bidirectional"))
    )
    (net (code "103") (name "RADIO_A_MOSI") (class "Default")
      (node (ref "U1") (pin "67") (pinfunction "RADIO_A_MOSI_67") (pintype "passive"))
      (node (ref "U3") (pin "17") (pinfunction "MOSI_RX_17") (pintype "bidirectional"))
    )
    (net (code "104") (name "RADIO_A_NRESET") (class "Default")
      (node (ref "U1") (pin "13") (pinfunction "RADIO_CTRL[3]_13") (pintype "passive"))
      (node (ref "U3") (pin "15") (pinfunction "NRESET_15") (pintype "bidirectional"))
    )
    (net (code "105") (name "RADIO_A_SCK") (class "Default")
      (node (ref "U1") (pin "65") (pinfunction "RADIO_A_SCK_65") (pintype "passive"))
      (node (ref "U3") (pin "18") (pinfunction "SCK_18") (pintype "bidirectional"))
    )
    (net (code "106") (name "RADIO_B_CLK_32M") (class "Default")
      (node (ref "R8") (pin "2") (pinfunction "2_2") (pintype "passive"))
      (node (ref "U2") (pin "14") (pinfunction "BUSY_14") (pintype "bidirectional"))
    )
    (net (code "107") (name "RADIO_B_CLK_O") (class "Default")
      (node (ref "U1") (pin "37") (pinfunction "RADIO_B_IQ[4]_37") (pintype "passive"))
      (node (ref "U2") (pin "11") (pinfunction "DIO5_11") (pintype "bidirectional"))
    )
    (net (code "108") (name "RADIO_B_CSN") (class "Default")
      (node (ref "U1") (pin "18") (pinfunction "RADIO_B_CSN_18") (pintype "passive"))
      (node (ref "U2") (pin "19") (pinfunction "NSS_19") (pintype "bidirectional"))
    )
    (net (code "109") (name "RADIO_B_IQ0") (class "Default")
      (node (ref "U1") (pin "35") (pinfunction "RADIO_B_IQ[0]_35") (pintype "passive"))
      (node (ref "U2") (pin "13") (pinfunction "DIO1_13") (pintype "bidirectional"))
    )
    (net (code "110") (name "RADIO_B_IQ1") (class "Default")
      (node (ref "U1") (pin "36") (pinfunction "RADIO_B_IQ[1]_36") (pintype "passive"))
      (node (ref "U2") (pin "12") (pinfunction "DIO2_12") (pintype "bidirectional"))
    )
    (net (code "111") (name "RADIO_B_IQ2") (class "Default")
      (node (ref "U1") (pin "38") (pinfunction "RADIO_B_IQ[2]_38") (pintype "passive"))
      (node (ref "U2") (pin "5") (pinfunction "DIO3_5") (pintype "bidirectional"))
    )
    (net (code "112") (name "RADIO_B_IQ3") (class "Default")
      (node (ref "U1") (pin "32") (pinfunction "RADIO_B_IQ[3]_32") (pintype "passive"))
      (node (ref "U2") (pin "21") (pinfunction "DIO4_21") (pintype "bidirectional"))
    )
    (net (code "113") (name "RADIO_B_MISO") (class "Default")
      (node (ref "U1") (pin "33") (pinfunction "RADIO_B_MISO_33") (pintype "passive"))
      (node (ref "U2") (pin "16") (pinfunction "MISO_TX_16") (pintype "bidirectional"))
    )
    (net (code "114") (name "RADIO_B_MOSI") (class "Default")
      (node (ref "U1") (pin "19") (pinfunction "RADIO_B_MOSI_19") (pintype "passive"))
      (node (ref "U2") (pin "17") (pinfunction "MOSI_RX_17") (pintype "bidirectional"))
    )
    (net (code "115") (name "RADIO_B_NRESET") (class "Default")
      (node (ref "U1") (pin "28") (pinfunction "RADIO_CTRL[9]_28") (pintype "passive"))
      (node (ref "U2") (pin "15") (pinfunction "NRESET_15") (pintype "bidirectional"))
    )
    (net (code "116") (name "RADIO_B_SCK") (class "Default")
      (node (ref "U1") (pin "21") (pinfunction "RADIO_B_SCK_21") (pintype "passive"))
      (node (ref "U2") (pin "18") (pinfunction "SCK_18") (pintype "bidirectional"))
    )
    (net (code "117") (name "RADIO_CTRL1") (class "Default")
      (node (ref "U1") (pin "11") (pinfunction "RADIO_CTRL[1]_11") (pintype "passive"))
    )
    (net (code "118") (name "RXTX_SW") (class "Default")
      (node (ref "C52") (pin "1") (pinfunction "1_1") (pintype "passive"))
      (node (ref "R34") (pin "2") (pinfunction "2_2") (pintype "passive"))
      (node (ref "U6") (pin "6") (pinfunction "CTX_6") (pintype "input"))
    )
    (net (code "119") (name "RX_ON") (class "Default")
      (node (ref "R21") (pin "1") (pinfunction "1_1") (pintype "passive"))
      (node (ref "U1") (pin "59") (pinfunction "GPIO[4]_59") (pintype "passive"))
    )
    (net (code "120") (name "SWCLK") (class "Default")
      (node (ref "P3") (pin "P$1") (pinfunction "P$1_P$1") (pintype "bidirectional"))
      (node (ref "U9") (pin "24") (pinfunction "PA14_24") (pintype "bidirectional"))
    )
    (net (code "121") (name "SWDIO") (class "Default")
      (node (ref "P4") (pin "P$1") (pinfunction "P$1_P$1") (pintype "bidirectional"))
      (node (ref "U9") (pin "23") (pinfunction "PA13_23") (pintype "bidirectional"))
    )
    (net (code "122") (name "SX1261_BUSY") (class "Default")
      (node (ref "J1") (pin "8") (pinfunction "8_8") (pintype "bidirectional"))
      (node (ref "P17") (pin "P$1") (pinfunction "P$1_P$1") (pintype "bidirectional"))
      (node (ref "U8") (pin "14") (pinfunction "BUSY_14") (pintype "bidirectional"))
      (node (ref "U9") (pin "9") (pinfunction "PA3_9") (pintype "bidirectional"))
    )
    (net (code "123") (name "SX1261_DIO1") (class "Default")
      (node (ref "J1") (pin "33") (pinfunction "33_33") (pintype "bidirectional"))
      (node (ref "P15") (pin "P$1") (pinfunction "P$1_P$1") (pintype "bidirectional"))
      (node (ref "U1") (pin "54") (pinfunction "GPIO[7]_54") (pintype "passive"))
      (node (ref "U8") (pin "13") (pinfunction "DIO1_13") (pintype "bidirectional"))
      (node (ref "U9") (pin "15") (pinfunction "PB1_15") (pintype "bidirectional"))
    )
    (net (code "124") (name "SX1261_DIO2") (class "Default")
      (node (ref "J1") (pin "31") (pinfunction "31_31") (pintype "bidirectional"))
      (node (ref "P14") (pin "P$1") (pinfunction "P$1_P$1") (pintype "bidirectional"))
      (node (ref "U8") (pin "12") (pinfunction "DIO2_12") (pintype "bidirectional"))
    )
    (net (code "125") (name "SX1261_NRESET") (class "Default")
      (node (ref "J1") (pin "10") (pinfunction "10_10") (pintype "bidirectional"))
      (node (ref "P18") (pin "P$1") (pinfunction "P$1_P$1") (pintype "bidirectional"))
      (node (ref "R40") (pin "1") (pinfunction "1_1") (pintype "passive"))
      (node (ref "U8") (pin "15") (pinfunction "NRESET_15") (pintype "bidirectional"))
      (node (ref "U9") (pin "18") (pinfunction "PA8_18") (pintype "bidirectional"))
    )
    (net (code "126") (name "SX1261_NSS") (class "Default")
      (node (ref "J1") (pin "25") (pinfunction "25_25") (pintype "bidirectional"))
      (node (ref "P13") (pin "P$1") (pinfunction "P$1_P$1") (pintype "bidirectional"))
      (node (ref "R39") (pin "1") (pinfunction "1_1") (pintype "passive"))
      (node (ref "R41") (pin "1") (pinfunction "1_1") (pintype "passive"))
      (node (ref "U9") (pin "14") (pinfunction "PB0_14") (pintype "bidirectional"))
    )
    (net (code "127") (name "SX1302_CSD") (class "Default")
      (node (ref "R33") (pin "1") (pinfunction "1_1") (pintype "passive"))
      (node (ref "R4") (pin "1") (pinfunction "1_1") (pintype "passive"))
      (node (ref "U1") (pin "10") (pinfunction "RADIO_CTRL[0]_10") (pintype "passive"))
    )
    (net (code "128") (name "SX1302_GPIO8") (class "Default")
      (node (ref "U1") (pin "53") (pinfunction "GPIO[8]_53") (pintype "passive"))
      (node (ref "U9") (pin "26") (pinfunction "PB3_26") (pintype "bidirectional"))
    )
    (net (code "129") (name "SX1302_PA_ON") (class "Default")
      (node (ref "R35") (pin "1") (pinfunction "1_1") (pintype "passive"))
      (node (ref "U1") (pin "16") (pinfunction "RADIO_CTRL[4]_16") (pintype "passive"))
    )
    (net (code "130") (name "SX1302_RESET") (class "Default")
      (node (ref "C63") (pin "2") (pinfunction "2_2") (pintype "passive"))
      (node (ref "D4") (pin "-") (pinfunction "-_-") (pintype "passive"))
      (node (ref "R5") (pin "2") (pinfunction "2_2") (pintype "passive"))
      (node (ref "U1") (pin "7") (pinfunction "RESET_7") (pintype "passive"))
      (node (ref "U9") (pin "8") (pinfunction "PA2_8") (pintype "bidirectional"))
    )
    (net (code "131") (name "SX1302_RXTX_SW") (class "Default")
      (node (ref "R34") (pin "1") (pinfunction "1_1") (pintype "passive"))
      (node (ref "U1") (pin "12") (pinfunction "RADIO_CTRL[2]_12") (pintype "passive"))
    )
    (net (code "132") (name "TCXO_32M_O") (class "Default")
      (node (ref "R24") (pin "2") (pinfunction "2_2") (pintype "passive"))
      (node (ref "R26") (pin "2") (pinfunction "2_2") (pintype "passive"))
      (node (ref "R28") (pin "2") (pinfunction "2_2") (pintype "passive"))
      (node (ref "R37") (pin "2") (pinfunction "2_2") (pintype "passive"))
    )
    (net (code "133") (name "TX_ON") (class "Default")
      (node (ref "R23") (pin "1") (pinfunction "1_1") (pintype "passive"))
      (node (ref "U1") (pin "63") (pinfunction "GPIO[2]_63") (pintype "passive"))
    )
    (net (code "134") (name "USB_D+") (class "Default")
      (node (ref "R9") (pin "2") (pinfunction "2_2") (pintype "passive"))
      (node (ref "U9") (pin "22") (pinfunction "PA12_22") (pintype "bidirectional"))
    )
    (net (code "135") (name "USB_D-") (class "Default")
      (node (ref "R7") (pin "2") (pinfunction "2_2") (pintype "passive"))
      (node (ref "U9") (pin "21") (pinfunction "PA11_21") (pintype "bidirectional"))
    )
    (net (code "136") (name "VCCIO33") (class "Default")
      (node (ref "C10") (pin "2") (pinfunction "2_2") (pintype "passive"))
      (node (ref "C12") (pin "2") (pinfunction "2_2") (pintype "passive"))
      (node (ref "C3") (pin "2") (pinfunction "2_2") (pintype "passive"))
      (node (ref "C4") (pin "2") (pinfunction "2_2") (pintype "passive"))
      (node (ref "C7") (pin "2") (pinfunction "2_2") (pintype "passive"))
      (node (ref "C8") (pin "2") (pinfunction "2_2") (pintype "passive"))
      (node (ref "C83") (pin "2") (pinfunction "2_2") (pintype "passive"))
      (node (ref "C84") (pin "2") (pinfunction "2_2") (pintype "passive"))
      (node (ref "Q1") (pin "3") (pinfunction "D_3") (pintype "passive"))
      (node (ref "R1") (pin "2") (pinfunction "2_2") (pintype "passive"))
      (node (ref "R19") (pin "2") (pinfunction "2_2") (pintype "passive"))
      (node (ref "R20") (pin "2") (pinfunction "2_2") (pintype "passive"))
      (node (ref "R4") (pin "2") (pinfunction "2_2") (pintype "passive"))
      (node (ref "R54") (pin "2") (pinfunction "2_2") (pintype "passive"))
      (node (ref "U1") (pin "14") (pinfunction "VCC_IO_14") (pintype "power_in"))
      (node (ref "U1") (pin "30") (pinfunction "VCC_IO_30") (pintype "power_in"))
      (node (ref "U1") (pin "47") (pinfunction "VCC_IO_47") (pintype "power_in"))
      (node (ref "U1") (pin "61") (pinfunction "VCC_IO_61") (pintype "power_in"))
    )
    (net (code "137") (name "VCC_FEM") (class "Default")
      (node (ref "C35") (pin "2") (pinfunction "2_2") (pintype "passive"))
      (node (ref "C36") (pin "2") (pinfunction "2_2") (pintype "passive"))
      (node (ref "C37") (pin "2") (pinfunction "2_2") (pintype "passive"))
      (node (ref "C38") (pin "2") (pinfunction "2_2") (pintype "passive"))
      (node (ref "C39") (pin "2") (pinfunction "2_2") (pintype "passive"))
      (node (ref "C82") (pin "2") (pinfunction "2_2") (pintype "passive"))
      (node (ref "FB6") (pin "2") (pinfunction "2_2") (pintype "passive"))
      (node (ref "L10") (pin "2") (pinfunction "2_2") (pintype "passive"))
      (node (ref "L11") (pin "2") (pinfunction "2_2") (pintype "passive"))
      (node (ref "U6") (pin "15") (pinfunction "VCC0_15") (pintype "power_in"))
    )
    (net (code "138") (name "VCORE12") (class "Default")
      (node (ref "C1") (pin "2") (pinfunction "2_2") (pintype "passive"))
      (node (ref "C11") (pin "2") (pinfunction "2_2") (pintype "passive"))
      (node (ref "C2") (pin "2") (pinfunction "2_2") (pintype "passive"))
      (node (ref "C5") (pin "2") (pinfunction "2_2") (pintype "passive"))
      (node (ref "C6") (pin "2") (pinfunction "2_2") (pintype "passive"))
      (node (ref "C79") (pin "2") (pinfunction "2_2") (pintype "passive"))
      (node (ref "C9") (pin "2") (pinfunction "2_2") (pintype "passive"))
      (node (ref "FB3") (pin "2") (pinfunction "2_2") (pintype "passive"))
      (node (ref "P23") (pin "P$1") (pinfunction "P$1_P$1") (pintype "bidirectional"))
      (node (ref "R18") (pin "2") (pinfunction "2_2") (pintype "passive"))
      (node (ref "U1") (pin "23") (pinfunction "VCC_CORE_23") (pintype "power_in"))
      (node (ref "U1") (pin "40") (pinfunction "VCC_CORE_40") (pintype "power_in"))
      (node (ref "U1") (pin "5") (pinfunction "VCC_CORE_5") (pintype "power_in"))
      (node (ref "U1") (pin "56") (pinfunction "VCC_CORE_56") (pintype "power_in"))
    )
    (net (code "139") (name "VDD_RADIO") (class "Default")
      (node (ref "C17") (pin "2") (pinfunction "2_2") (pintype "passive"))
      (node (ref "C23") (pin "2") (pinfunction "2_2") (pintype "passive"))
      (node (ref "C57") (pin "2") (pinfunction "2_2") (pintype "passive"))
      (node (ref "C81") (pin "2") (pinfunction "2_2") (pintype "passive"))
      (node (ref "FB1") (pin "1") (pinfunction "1_1") (pintype "passive"))
      (node (ref "FB5") (pin "2") (pinfunction "2_2") (pintype "passive"))
      (node (ref "R25") (pin "2") (pinfunction "2_2") (pintype "passive"))
      (node (ref "R27") (pin "2") (pinfunction "2_2") (pintype "passive"))
      (node (ref "R36") (pin "2") (pinfunction "2_2") (pintype "passive"))
      (node (ref "R39") (pin "2") (pinfunction "2_2") (pintype "passive"))
      (node (ref "R40") (pin "2") (pinfunction "2_2") (pintype "passive"))
      (node (ref "U2") (pin "10") (pinfunction "VBAT_DIO_10") (pintype "bidirectional"))
      (node (ref "U2") (pin "9") (pinfunction "VBAT_RF_9") (pintype "bidirectional"))
      (node (ref "U3") (pin "10") (pinfunction "VBAT_DIO_10") (pintype "bidirectional"))
      (node (ref "U3") (pin "9") (pinfunction "VBAT_RF_9") (pintype "bidirectional"))
      (node (ref "U8") (pin "10") (pinfunction "VBAT_10") (pintype "bidirectional"))
      (node (ref "U8") (pin "11") (pinfunction "VBAT_IO_11") (pintype "bidirectional"))
    )
    (net (code "140") (name "unconnected-(J1-1V5-Pad6)") (class "Default")
      (node (ref "J1") (pin "6") (pinfunction "1V5_6") (pintype "bidirectional"))
    )
    (net (code "141") (name "unconnected-(J1-1V5-Pad28)") (class "Default")
      (node (ref "J1") (pin "28") (pinfunction "1V5_28") (pintype "bidirectional"))
    )
    (net (code "142") (name "unconnected-(J1-1V5-Pad48)") (class "Default")
      (node (ref "J1") (pin "48") (pinfunction "1V5_48") (pintype "bidirectional"))
    )
    (net (code "143") (name "unconnected-(J1-Pad1)") (class "Default")
      (node (ref "J1") (pin "1") (pinfunction "1_1") (pintype "bidirectional"))
    )
    (net (code "144") (name "unconnected-(J1-Pad3)") (class "Default")
      (node (ref "J1") (pin "3") (pinfunction "3_3") (pintype "bidirectional"))
    )
    (net (code "145") (name "unconnected-(J1-Pad5)") (class "Default")
      (node (ref "J1") (pin "5") (pinfunction "5_5") (pintype "bidirectional"))
    )
    (net (code "146") (name "unconnected-(J1-Pad7)") (class "Default")
      (node (ref "J1") (pin "7") (pinfunction "7_7") (pintype "bidirectional"))
    )
    (net (code "147") (name "unconnected-(J1-Pad11)") (class "Default")
      (node (ref "J1") (pin "11") (pinfunction "11_11") (pintype "bidirectional"))
    )
    (net (code "148") (name "unconnected-(J1-Pad12)") (class "Default")
      (node (ref "J1") (pin "12") (pinfunction "12_12") (pintype "bidirectional"))
    )
    (net (code "149") (name "unconnected-(J1-Pad13)") (class "Default")
      (node (ref "J1") (pin "13") (pinfunction "13_13") (pintype "bidirectional"))
    )
    (net (code "150") (name "unconnected-(J1-Pad14)") (class "Default")
      (node (ref "J1") (pin "14") (pinfunction "14_14") (pintype "bidirectional"))
    )
    (net (code "151") (name "unconnected-(J1-Pad16)") (class "Default")
      (node (ref "J1") (pin "16") (pinfunction "16_16") (pintype "bidirectional"))
    )
    (net (code "152") (name "unconnected-(J1-Pad17)") (class "Default")
      (node (ref "J1") (pin "17") (pinfunction "17_17") (pintype "bidirectional"))
    )
    (net (code "153") (name "unconnected-(J1-Pad20)") (class "Default")
      (node (ref "J1") (pin "20") (pinfunction "20_20") (pintype "bidirectional"))
    )
    (net (code "154") (name "unconnected-(J1-Pad23)") (class "Default")
      (node (ref "J1") (pin "23") (pinfunction "23_23") (pintype "bidirectional"))
    )
    (net (code "155") (name "unconnected-(J1-Pad42)") (class "Default")
      (node (ref "J1") (pin "42") (pinfunction "42_42") (pintype "bidirectional"))
    )
    (net (code "156") (name "unconnected-(J1-Pad44)") (class "Default")
      (node (ref "J1") (pin "44") (pinfunction "44_44") (pintype "bidirectional"))
    )
    (net (code "157") (name "unconnected-(J1-Pad46)") (class "Default")
      (node (ref "J1") (pin "46") (pinfunction "46_46") (pintype "bidirectional"))
    )
    (net (code "158") (name "unconnected-(U1-GPIO[1]-Pad64)") (class "Default")
      (node (ref "U1") (pin "64") (pinfunction "GPIO[1]_64") (pintype "passive"))
    )
    (net (code "159") (name "unconnected-(U1-GPIO[3]-Pad60)") (class "Default")
      (node (ref "U1") (pin "60") (pinfunction "GPIO[3]_60") (pintype "passive"))
    )
    (net (code "160") (name "unconnected-(U1-GPIO[5]-Pad58)") (class "Default")
      (node (ref "U1") (pin "58") (pinfunction "GPIO[5]_58") (pintype "passive"))
    )
    (net (code "161") (name "unconnected-(U1-RADIO_CTRL[5]-Pad17)") (class "Default")
      (node (ref "U1") (pin "17") (pinfunction "RADIO_CTRL[5]_17") (pintype "passive"))
    )
    (net (code "162") (name "unconnected-(U1-RADIO_CTRL[6]-Pad22)") (class "Default")
      (node (ref "U1") (pin "22") (pinfunction "RADIO_CTRL[6]_22") (pintype "passive"))
    )
    (net (code "163") (name "unconnected-(U1-RADIO_CTRL[7]-Pad26)") (class "Default")
      (node (ref "U1") (pin "26") (pinfunction "RADIO_CTRL[7]_26") (pintype "passive"))
    )
    (net (code "164") (name "unconnected-(U1-RADIO_CTRL[8]-Pad27)") (class "Default")
      (node (ref "U1") (pin "27") (pinfunction "RADIO_CTRL[8]_27") (pintype "passive"))
    )
    (net (code "165") (name "unconnected-(U1-RADIO_CTRL[10]-Pad29)") (class "Default")
      (node (ref "U1") (pin "29") (pinfunction "RADIO_CTRL[10]_29") (pintype "passive"))
    )
    (net (code "166") (name "unconnected-(U1-RADIO_CTRL[11]-Pad31)") (class "Default")
      (node (ref "U1") (pin "31") (pinfunction "RADIO_CTRL[11]_31") (pintype "passive"))
    )
    (net (code "167") (name "unconnected-(U2-RFO-Pad24)") (class "Default")
      (node (ref "U2") (pin "24") (pinfunction "RFO_24") (pintype "bidirectional"))
    )
    (net (code "168") (name "unconnected-(U2-VR_PA-Pad1)") (class "Default")
      (node (ref "U2") (pin "1") (pinfunction "VR_PA_1") (pintype "bidirectional"))
    )
    (net (code "169") (name "unconnected-(U2-XTB-Pad4)") (class "Default")
      (node (ref "U2") (pin "4") (pinfunction "XTB_4") (pintype "bidirectional"))
    )
    (net (code "170") (name "unconnected-(U3-XTB-Pad4)") (class "Default")
      (node (ref "U3") (pin "4") (pinfunction "XTB_4") (pintype "bidirectional"))
    )
    (net (code "171") (name "unconnected-(U6-N{slash}C-Pad14)") (class "Default")
      (node (ref "U6") (pin "14") (pinfunction "N/C_14") (pintype "passive"))
    )
    (net (code "172") (name "unconnected-(U6-TX_ALT-Pad3)") (class "Default")
      (node (ref "U6") (pin "3") (pinfunction "TX_ALT_3") (pintype "passive"))
    )
    (net (code "173") (name "unconnected-(U8-RFO-Pad23)") (class "Default")
      (node (ref "U8") (pin "23") (pinfunction "RFO_23") (pintype "bidirectional"))
    )
    (net (code "174") (name "unconnected-(U8-VR_PA-Pad24)") (class "Default")
      (node (ref "U8") (pin "24") (pinfunction "VR_PA_24") (pintype "bidirectional"))
    )
    (net (code "175") (name "unconnected-(U8-XTB-Pad4)") (class "Default")
      (node (ref "U8") (pin "4") (pinfunction "XTB_4") (pintype "bidirectional"))
    )
    (net (code "176") (name "unconnected-(U9-PA9-Pad19)") (class "Default")
      (node (ref "U9") (pin "19") (pinfunction "PA9_19") (pintype "bidirectional"))
    )
    (net (code "177") (name "unconnected-(U9-PA10-Pad20)") (class "Default")
      (node (ref "U9") (pin "20") (pinfunction "PA10_20") (pintype "bidirectional"))
    )
    (net (code "178") (name "unconnected-(U9-PA15-Pad25)") (class "Default")
      (node (ref "U9") (pin "25") (pinfunction "PA15_25") (pintype "bidirectional"))
    )
    (net (code "179") (name "unconnected-(U9-PB5-Pad28)") (class "Default")
      (node (ref "U9") (pin "28") (pinfunction "PB5_28") (pintype "bidirectional"))
    )
  )
)
